# cape.net
KiCad netlist of a schematic drawn in EAGLE
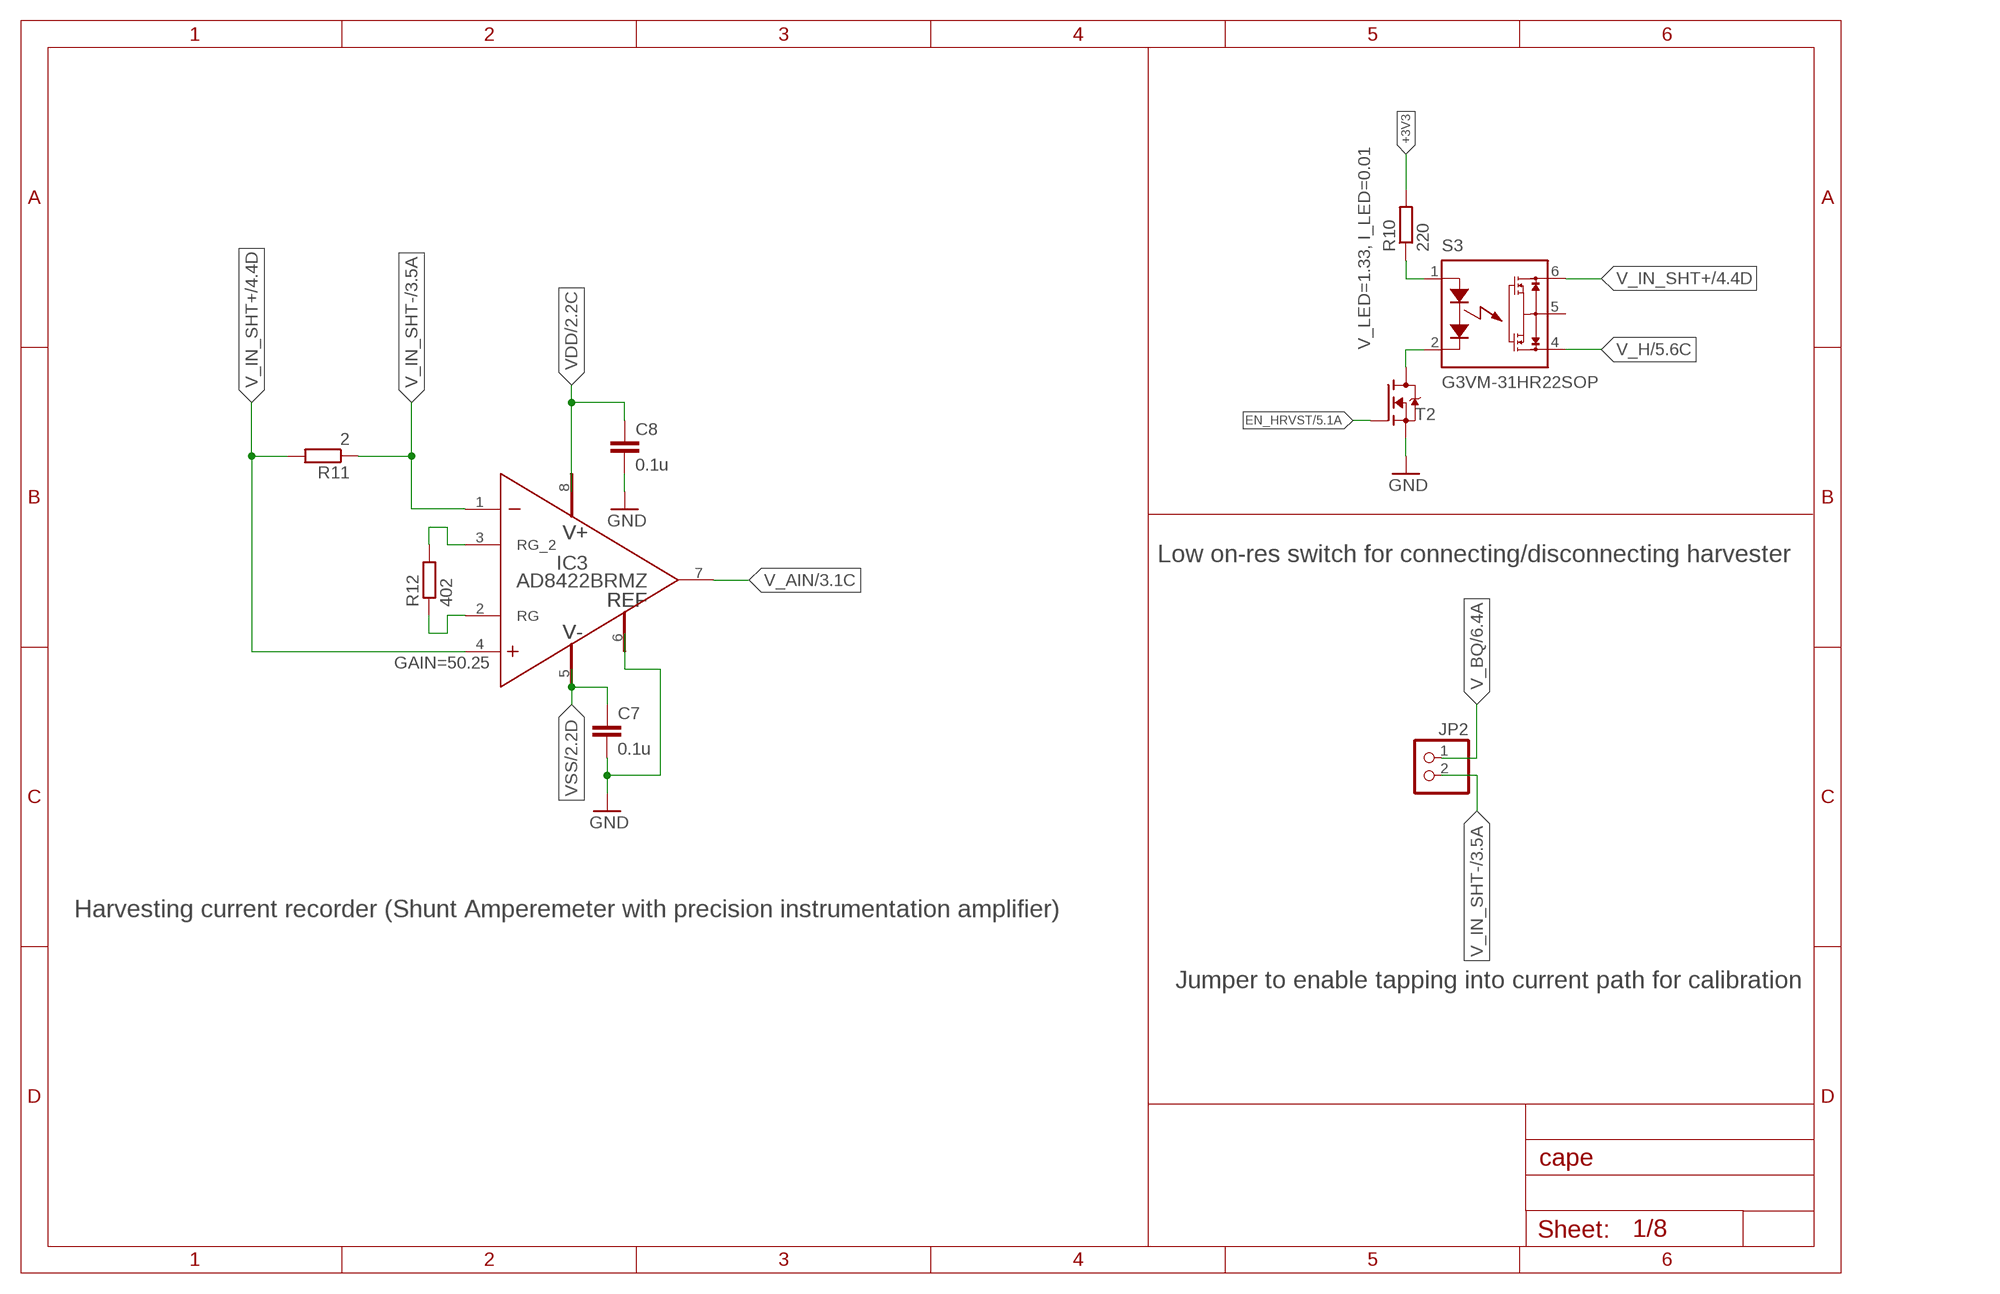
[diagram p0: schematic, sheet 1]
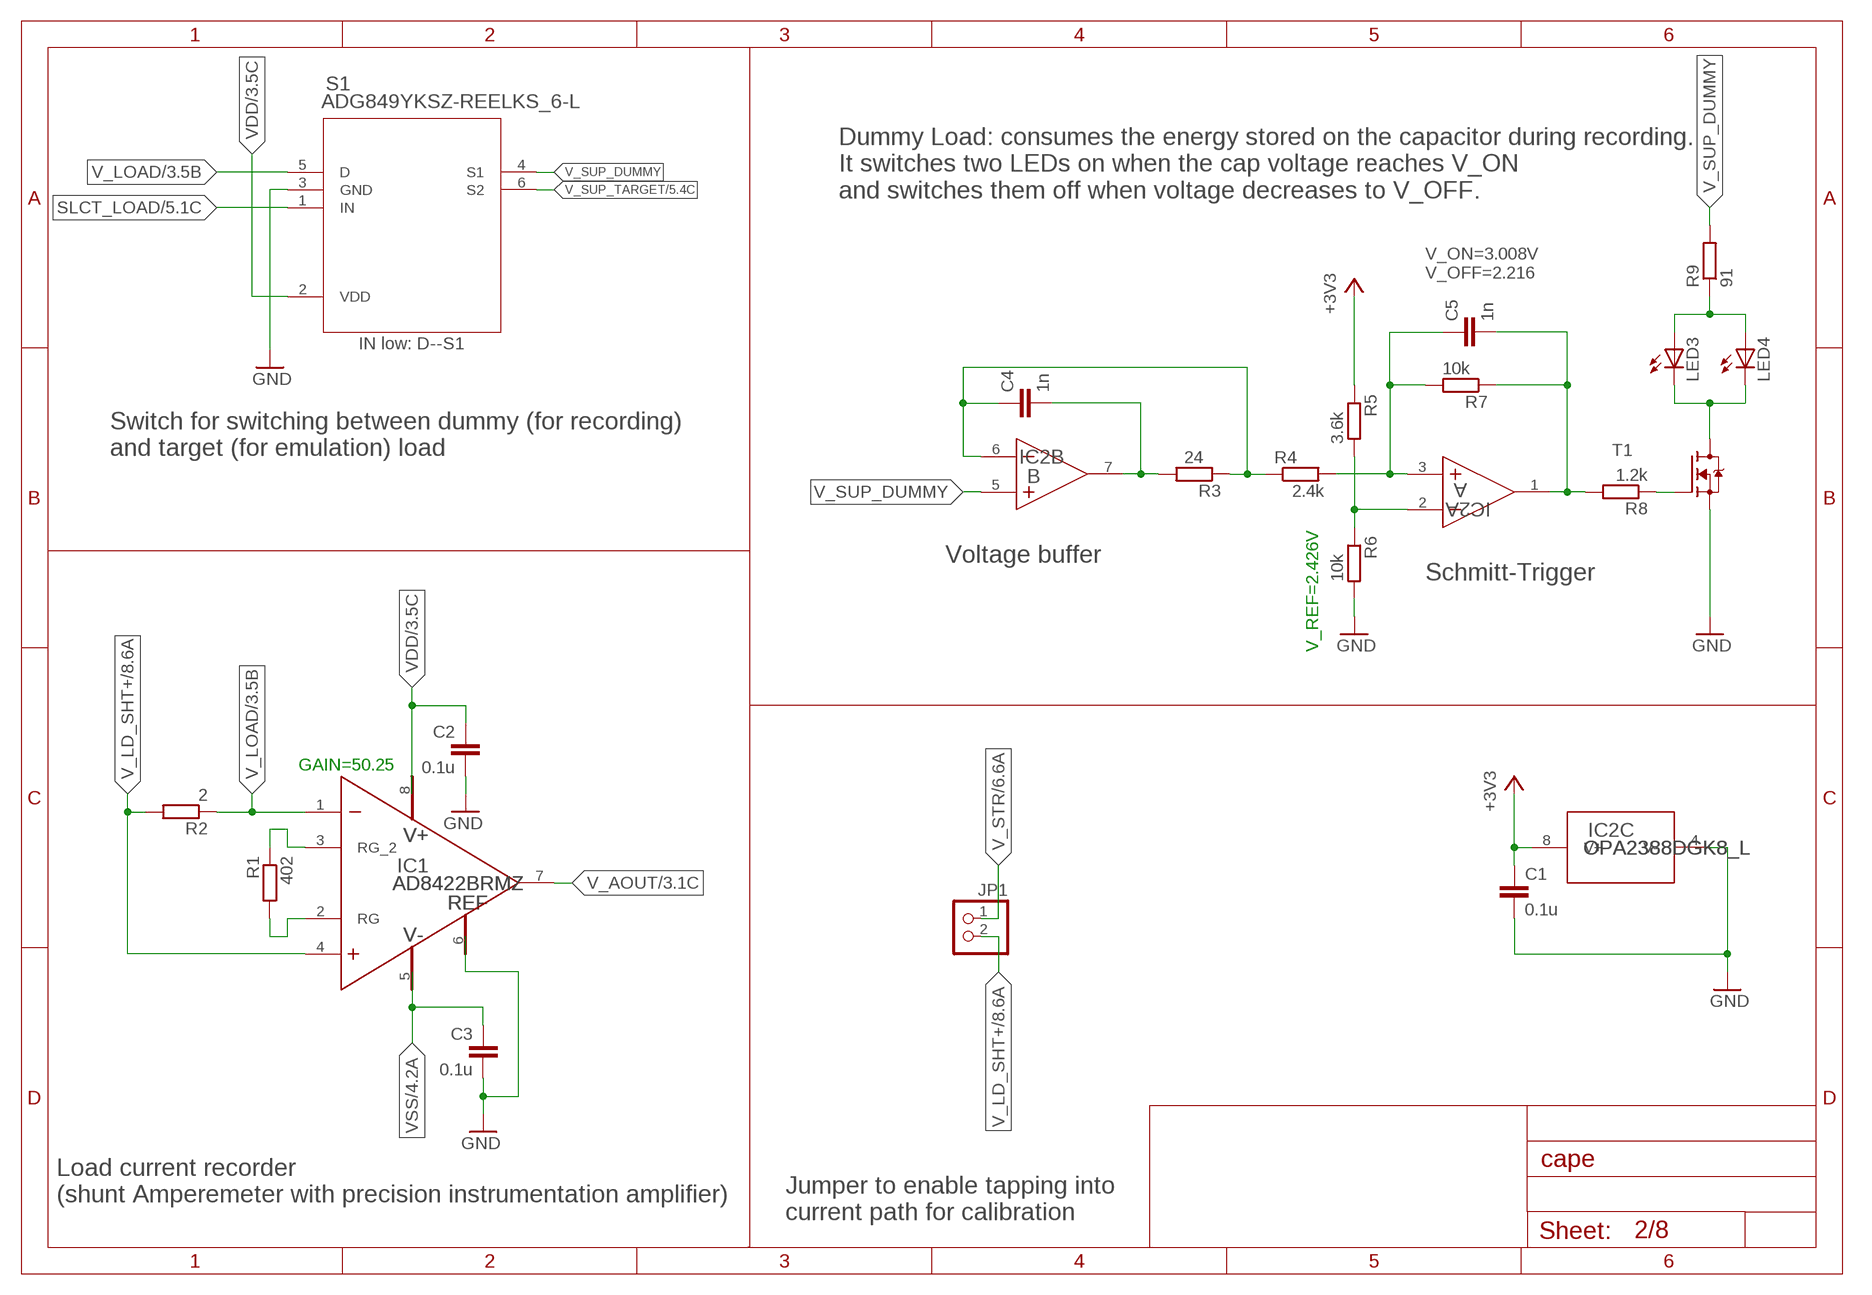
[diagram p1: schematic, sheet 2]
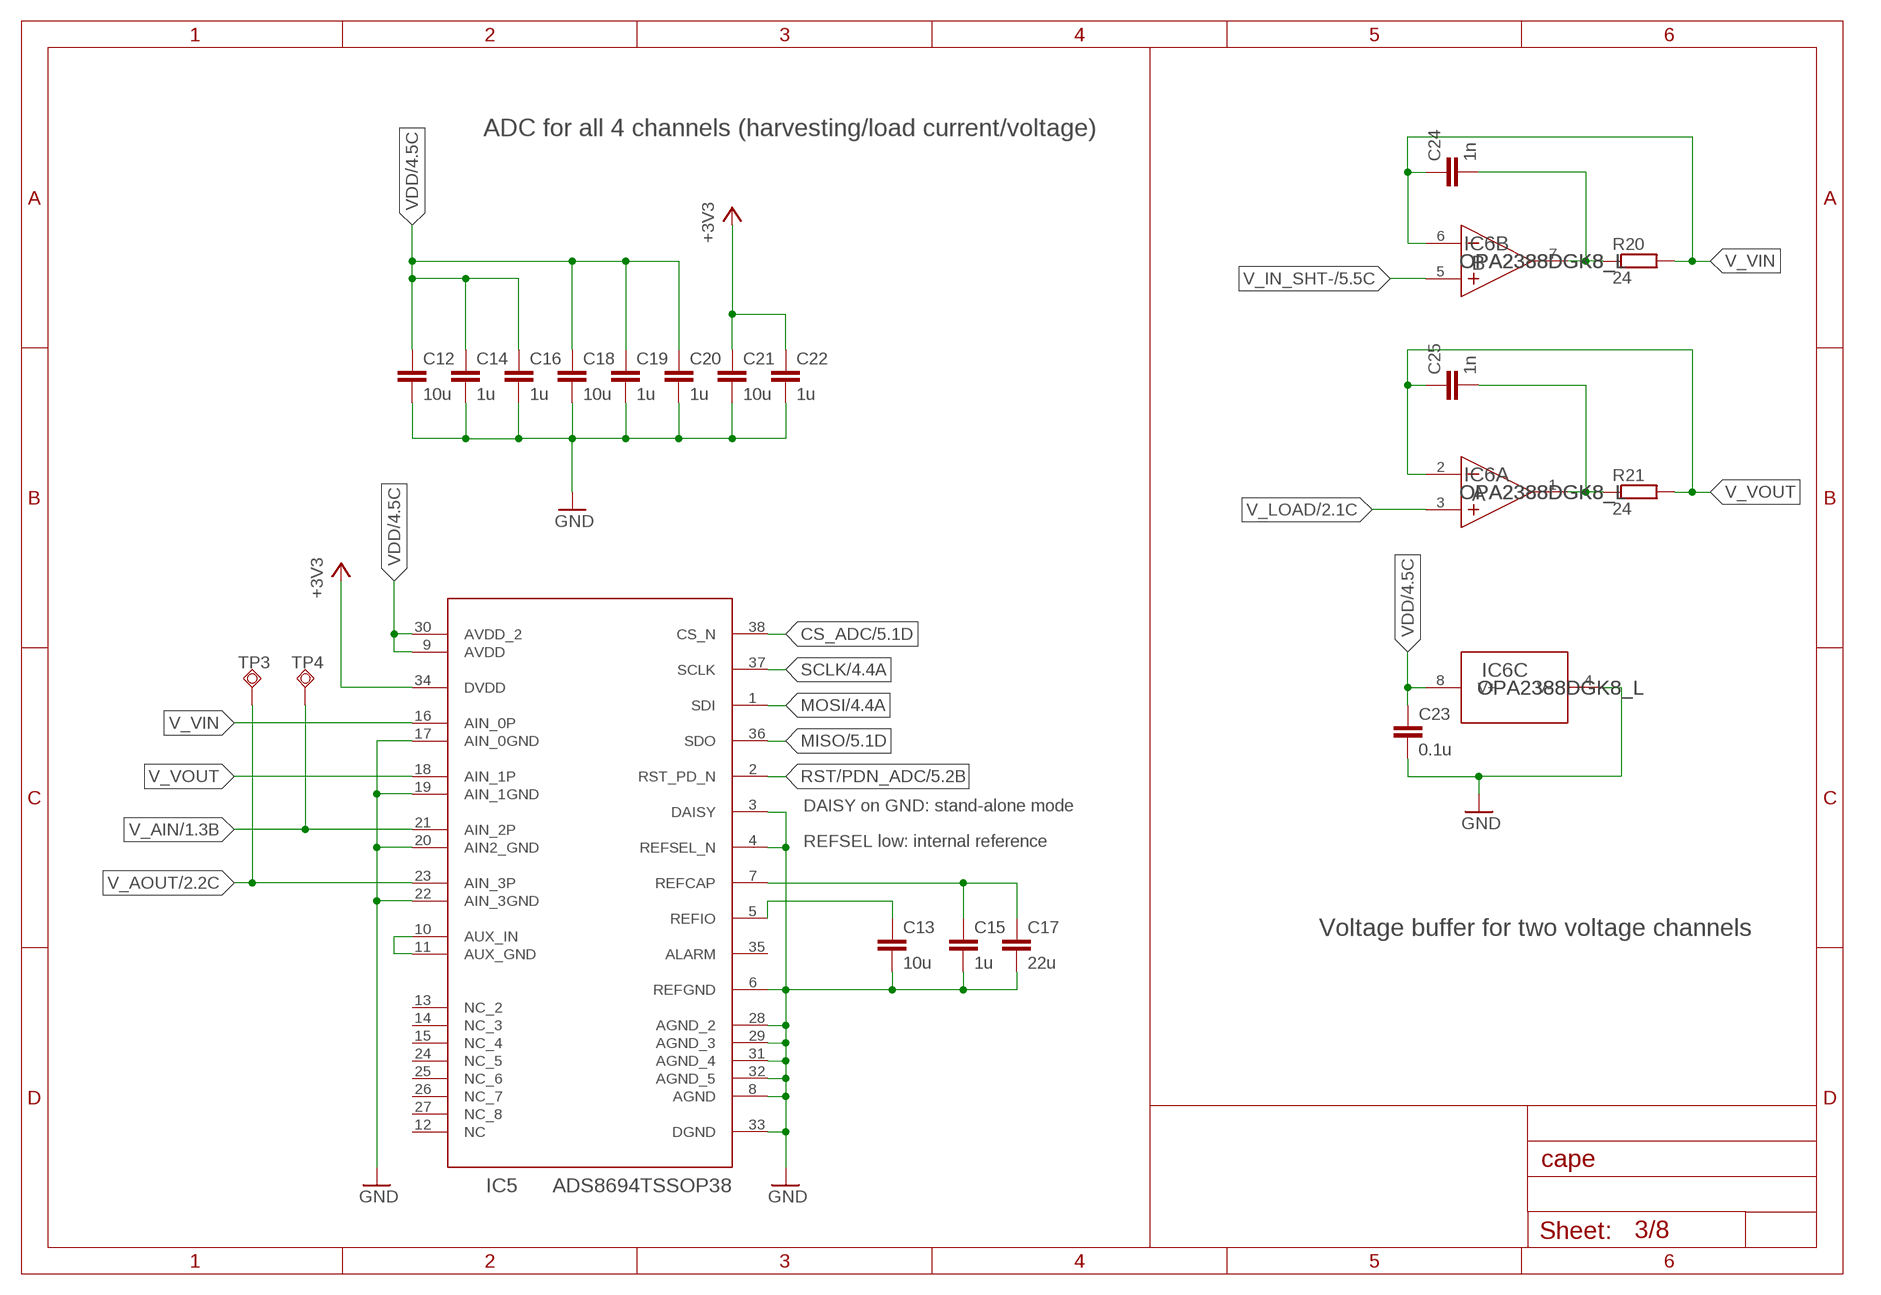
[diagram p2: schematic, sheet 3]
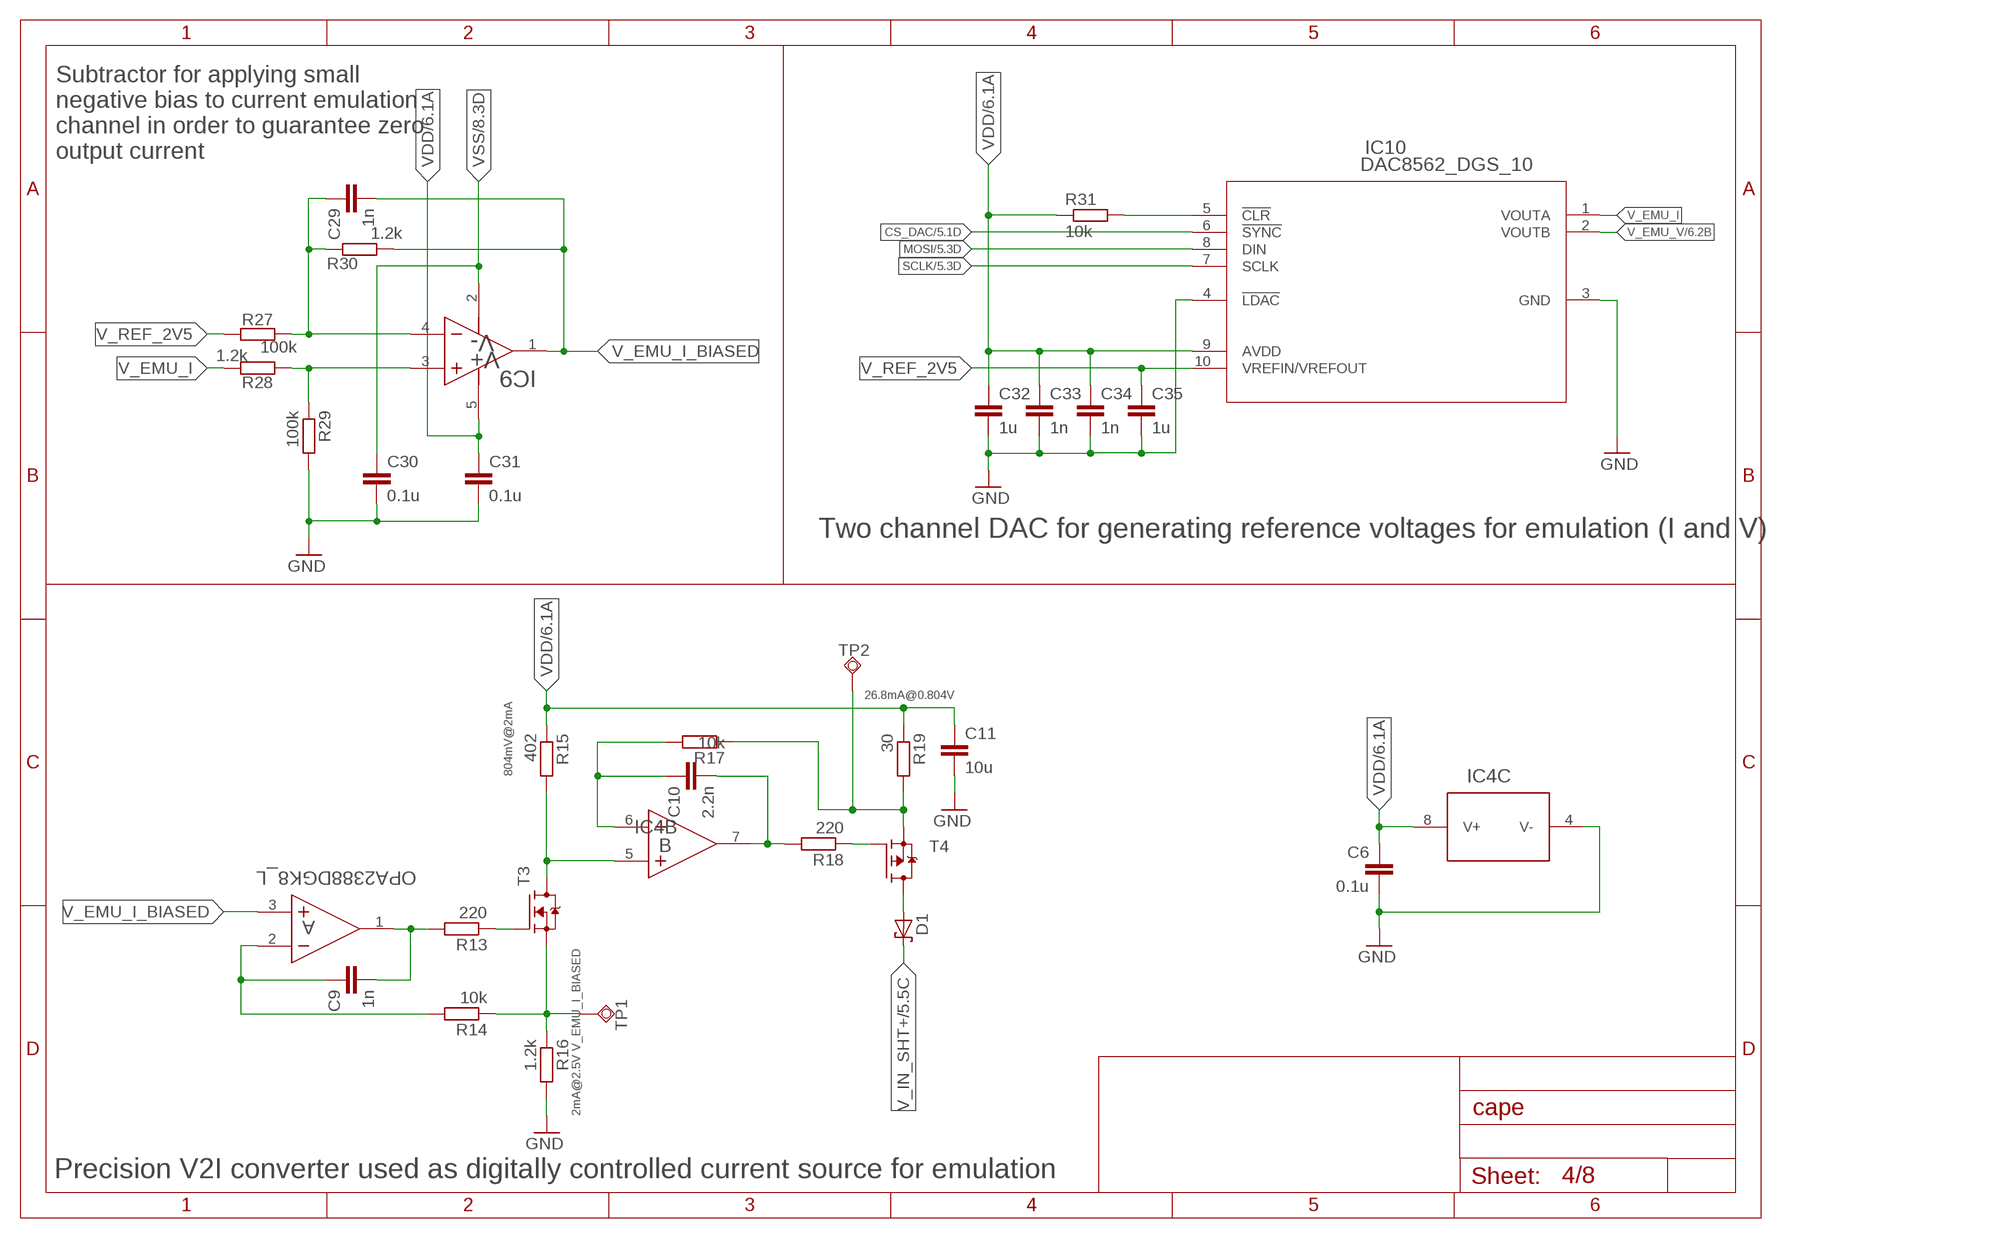
[diagram p3: schematic, sheet 4]
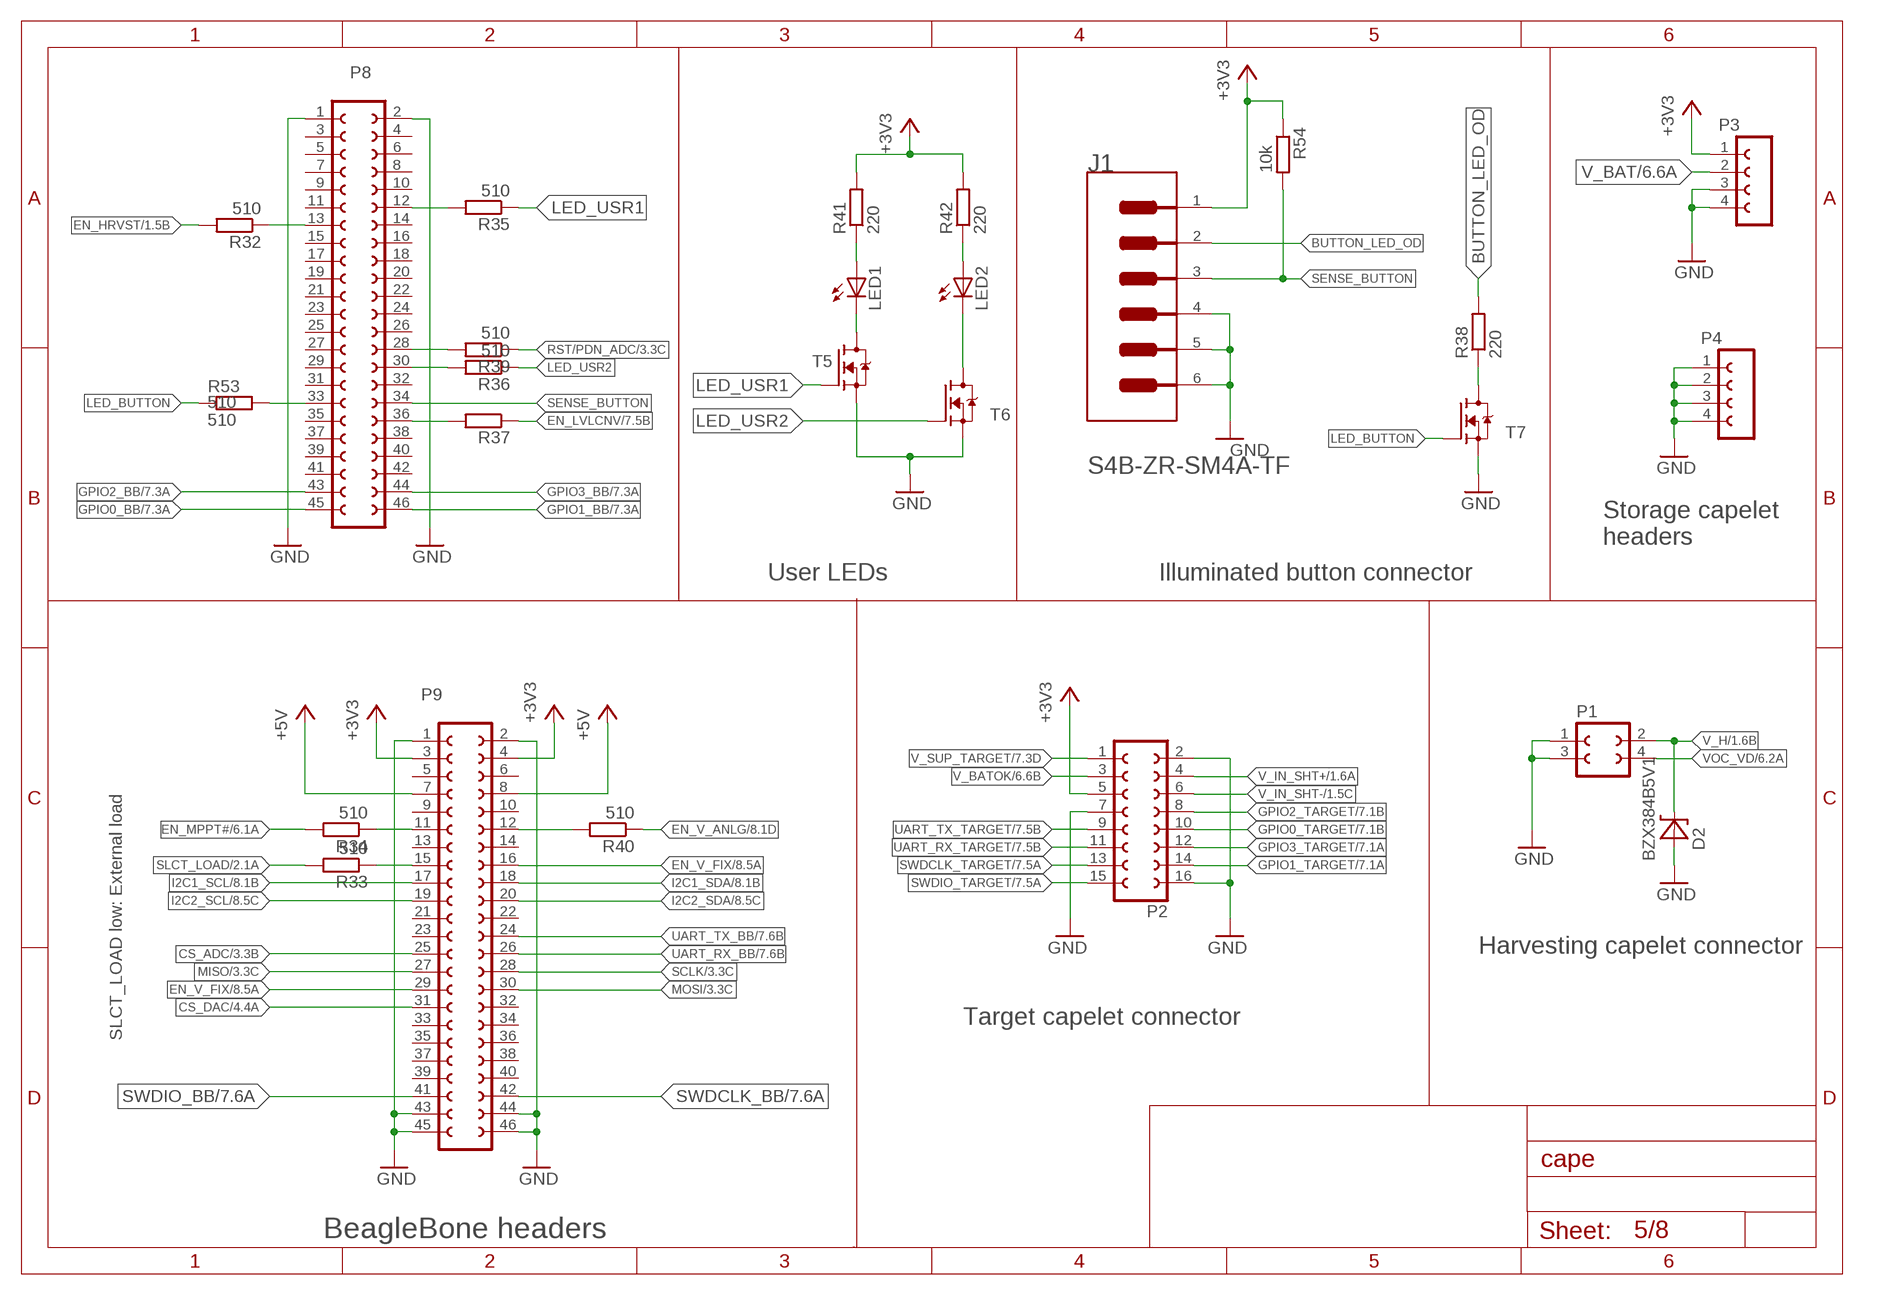
[diagram p4: schematic, sheet 5]
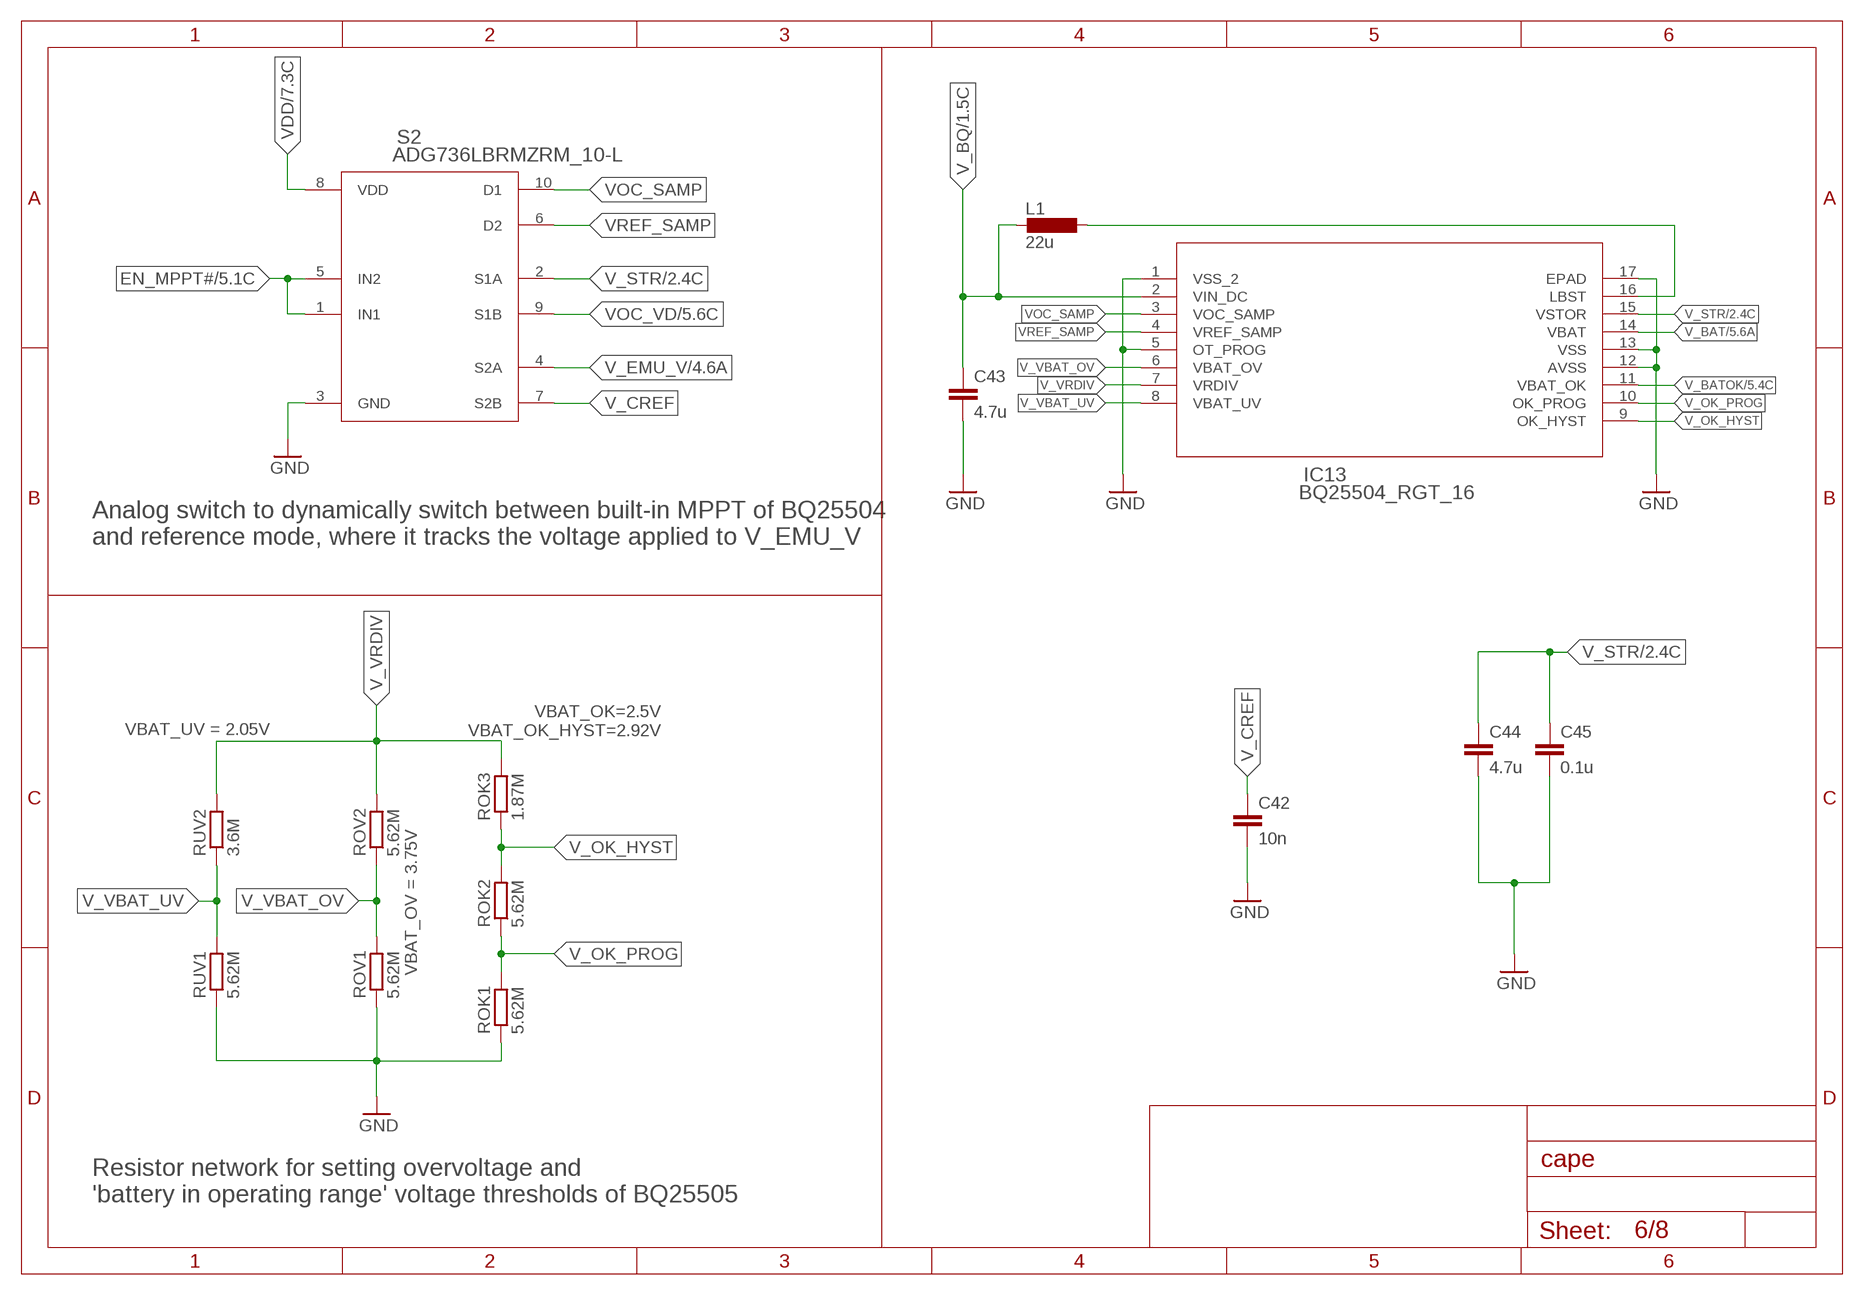
[diagram p5: schematic, sheet 6]
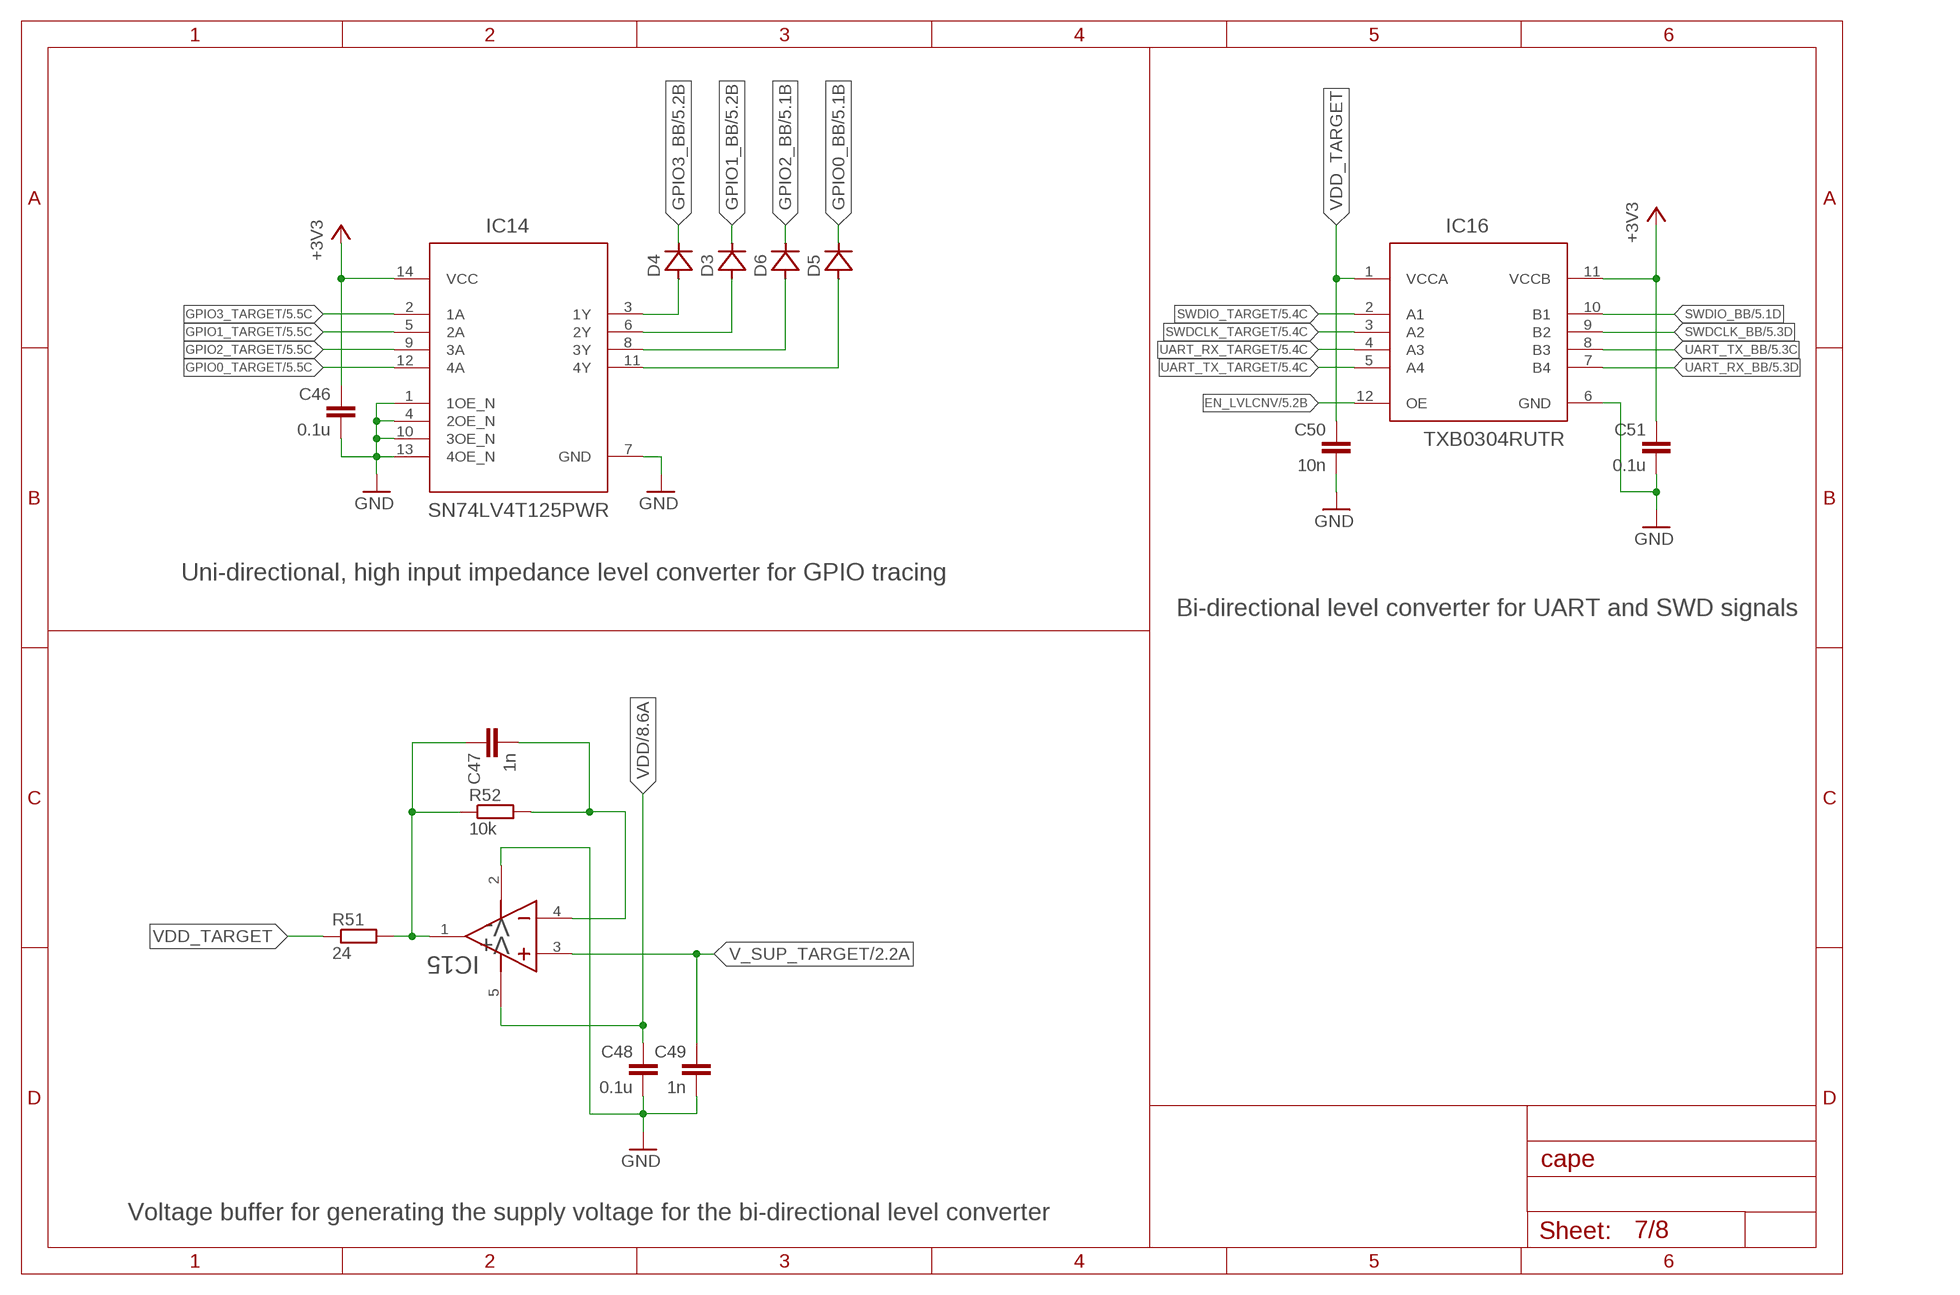
[diagram p6: schematic, sheet 7]
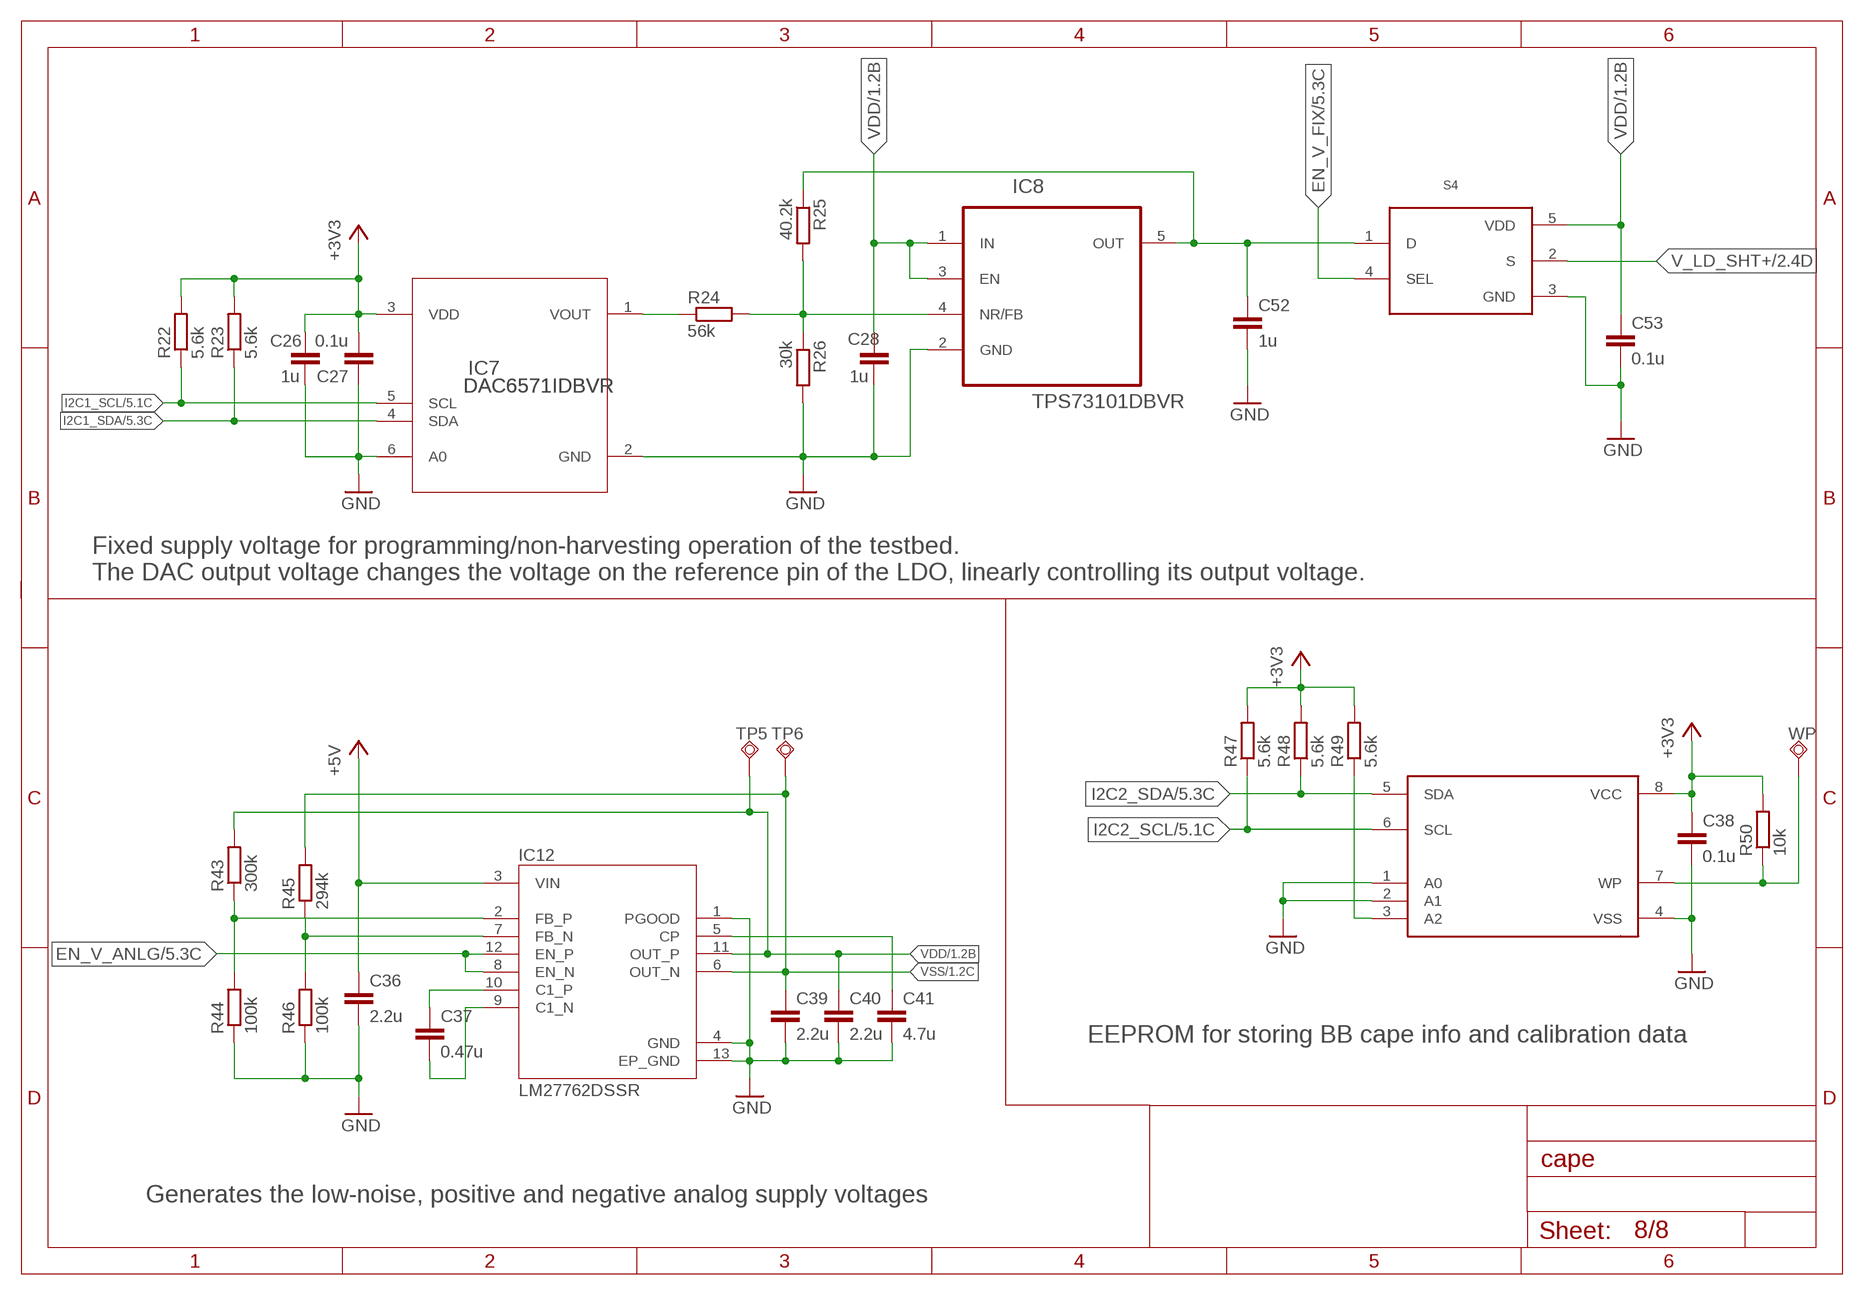
[diagram p7: schematic, sheet 8]

(export (version "E")
  (design (tool "Eeschema 10.0.6"))
  (components
    (comp (ref "C1")
      (value "0.1u")
      (footprint "eagle-import:CAPC1005X55")
      (libsource (lib "eagle-import") (part "C_SMD0402"))
    )
    (comp (ref "C2")
      (value "0.1u")
      (footprint "eagle-import:CAPC1005X55")
      (libsource (lib "eagle-import") (part "C_SMD0402"))
    )
    (comp (ref "C3")
      (value "0.1u")
      (footprint "eagle-import:CAPC1005X55")
      (libsource (lib "eagle-import") (part "C_SMD0402"))
    )
    (comp (ref "C4")
      (value "1n")
      (footprint "eagle-import:CAPC1005X55")
      (libsource (lib "eagle-import") (part "C_SMD0402"))
    )
    (comp (ref "C5")
      (value "1n")
      (footprint "eagle-import:CAPC1005X55")
      (libsource (lib "eagle-import") (part "C_SMD0402"))
    )
    (comp (ref "IC1")
      (value "AD8422BRMZ")
      (footprint "eagle-import:RM_8-L")
      (libsource (lib "eagle-import") (part "AD8422BRMZ"))
    )
    (comp (ref "IC2")
      (value "OPA2388DGK8_L")
      (footprint "eagle-import:DGK8-L")
      (libsource (lib "eagle-import") (part "OPA2388DGK8_L"))
    )
    (comp (ref "JP1")
      (value "PINHD-1X2")
      (footprint "eagle-import:1X02")
      (libsource (lib "eagle-import") (part "PINHD-1X2"))
    )
    (comp (ref "LED3")
      (value "598-8130-107FLED_0805")
      (footprint "eagle-import:LEDC2012X75")
      (libsource (lib "eagle-import") (part "598-8130-107FLED_0805"))
    )
    (comp (ref "LED4")
      (value "598-8130-107FLED_0805")
      (footprint "eagle-import:LEDC2012X75")
      (libsource (lib "eagle-import") (part "598-8130-107FLED_0805"))
    )
    (comp (ref "R1")
      (value "402")
      (footprint "eagle-import:RESC1608X55")
      (libsource (lib "eagle-import") (part "R_SMD0603"))
    )
    (comp (ref "R2")
      (value "2")
      (footprint "eagle-import:RESC1608X55")
      (libsource (lib "eagle-import") (part "R_SMD0603"))
    )
    (comp (ref "R3")
      (value "24")
      (footprint "eagle-import:RESC1005X40")
      (libsource (lib "eagle-import") (part "R_SMD0402"))
    )
    (comp (ref "R4")
      (value "2.4k")
      (footprint "eagle-import:RESC1005X40")
      (libsource (lib "eagle-import") (part "R_SMD0402"))
    )
    (comp (ref "R5")
      (value "3.6k")
      (footprint "eagle-import:RESC1005X40")
      (libsource (lib "eagle-import") (part "R_SMD0402"))
    )
    (comp (ref "R6")
      (value "10k")
      (footprint "eagle-import:RESC1005X40")
      (libsource (lib "eagle-import") (part "R_SMD0402"))
    )
    (comp (ref "R7")
      (value "10k")
      (footprint "eagle-import:RESC1005X40")
      (libsource (lib "eagle-import") (part "R_SMD0402"))
    )
    (comp (ref "R8")
      (value "1.2k")
      (footprint "eagle-import:RESC1005X40")
      (libsource (lib "eagle-import") (part "R_SMD0402"))
    )
    (comp (ref "R9")
      (value "91")
      (footprint "eagle-import:RESC1608X55")
      (libsource (lib "eagle-import") (part "R_SMD0603"))
    )
    (comp (ref "S1")
      (value "ADG849YKSZ-REELKS_6-L")
      (footprint "eagle-import:KS_6-L")
      (libsource (lib "eagle-import") (part "ADG849YKSZ-REELKS_6-L"))
    )
    (comp (ref "T1")
      (value "SI2374DSSOT23-VSHAY")
      (footprint "eagle-import:SOT95P237X112-3")
      (libsource (lib "eagle-import") (part "SI2374DSSOT23-VSHAY"))
    )
    (comp (ref "C26")
      (value "1u")
      (footprint "eagle-import:CAPC1608X95")
      (libsource (lib "eagle-import") (part "C_SMD0603"))
    )
    (comp (ref "C27")
      (value "0.1u")
      (footprint "eagle-import:CAPC1005X55")
      (libsource (lib "eagle-import") (part "C_SMD0402"))
    )
    (comp (ref "C28")
      (value "1u")
      (footprint "eagle-import:CAPC1608X95")
      (libsource (lib "eagle-import") (part "C_SMD0603"))
    )
    (comp (ref "C36")
      (value "2.2u")
      (footprint "eagle-import:CAPC2012X145")
      (libsource (lib "eagle-import") (part "C_SMD0805"))
    )
    (comp (ref "C37")
      (value "0.47u")
      (footprint "eagle-import:CAPC1608X95")
      (libsource (lib "eagle-import") (part "C_SMD0603"))
    )
    (comp (ref "C38")
      (value "0.1u")
      (footprint "eagle-import:CAPC1005X55")
      (libsource (lib "eagle-import") (part "C_SMD0402"))
    )
    (comp (ref "C39")
      (value "2.2u")
      (footprint "eagle-import:CAPC2012X145")
      (libsource (lib "eagle-import") (part "C_SMD0805"))
    )
    (comp (ref "C40")
      (value "2.2u")
      (footprint "eagle-import:CAPC2012X145")
      (libsource (lib "eagle-import") (part "C_SMD0805"))
    )
    (comp (ref "C41")
      (value "4.7u")
      (footprint "eagle-import:CAPC2012X145")
      (libsource (lib "eagle-import") (part "C_SMD0805"))
    )
    (comp (ref "C52")
      (value "1u")
      (footprint "eagle-import:CAPC1608X95")
      (libsource (lib "eagle-import") (part "shepherd_C_SMD0603"))
    )
    (comp (ref "C53")
      (value "0.1u")
      (footprint "eagle-import:CAPC1005X55")
      (libsource (lib "eagle-import") (part "C_SMD0402"))
    )
    (comp (ref "IC7")
      (value "DAC6571IDBVR")
      (footprint "eagle-import:DAC6571IDBVR")
      (libsource (lib "eagle-import") (part "DAC6571IDBVR"))
    )
    (comp (ref "IC8")
      (value "TPS73101DBVR")
      (footprint "eagle-import:SOT95P280X145-5N")
      (fields (field (name "MF") "Texas Instruments"))
      (libsource (lib "eagle-import") (part "TPS73101DBVR"))
    )
    (comp (ref "IC11")
      (value "CAT24C256WI-GT3")
      (footprint "eagle-import:SO08")
      (libsource (lib "eagle-import") (part "CAT24C256WI-GT3"))
    )
    (comp (ref "IC12")
      (value "LM27762DSSR")
      (footprint "eagle-import:VREG_LM27762DSSR")
      (fields (field (name "MF") "Texas Instruments"))
      (libsource (lib "eagle-import") (part "LM27762DSSR"))
    )
    (comp (ref "R22")
      (value "5.6k")
      (footprint "eagle-import:RESC1005X40")
      (libsource (lib "eagle-import") (part "R_SMD0402"))
    )
    (comp (ref "R23")
      (value "5.6k")
      (footprint "eagle-import:RESC1005X40")
      (libsource (lib "eagle-import") (part "R_SMD0402"))
    )
    (comp (ref "R24")
      (value "56k")
      (footprint "eagle-import:RESC1005X40")
      (libsource (lib "eagle-import") (part "R_SMD0402"))
    )
    (comp (ref "R25")
      (value "40.2k")
      (footprint "eagle-import:RESC1005X40")
      (libsource (lib "eagle-import") (part "R_SMD0402"))
    )
    (comp (ref "R26")
      (value "30k")
      (footprint "eagle-import:RESC1005X40")
      (libsource (lib "eagle-import") (part "R_SMD0402"))
    )
    (comp (ref "R43")
      (value "300k")
      (footprint "eagle-import:RESC1005X40")
      (libsource (lib "eagle-import") (part "R_SMD0402"))
    )
    (comp (ref "R44")
      (value "100k")
      (footprint "eagle-import:RESC1005X40")
      (libsource (lib "eagle-import") (part "R_SMD0402"))
    )
    (comp (ref "R45")
      (value "294k")
      (footprint "eagle-import:RESC1005X40")
      (libsource (lib "eagle-import") (part "R_SMD0402"))
    )
    (comp (ref "R46")
      (value "100k")
      (footprint "eagle-import:RESC1005X40")
      (libsource (lib "eagle-import") (part "R_SMD0402"))
    )
    (comp (ref "R47")
      (value "5.6k")
      (footprint "eagle-import:RESC1005X40")
      (libsource (lib "eagle-import") (part "R_SMD0402"))
    )
    (comp (ref "R48")
      (value "5.6k")
      (footprint "eagle-import:RESC1005X40")
      (libsource (lib "eagle-import") (part "R_SMD0402"))
    )
    (comp (ref "R49")
      (value "5.6k")
      (footprint "eagle-import:RESC1005X40")
      (libsource (lib "eagle-import") (part "R_SMD0402"))
    )
    (comp (ref "R50")
      (value "10k")
      (footprint "eagle-import:RESC1005X40")
      (libsource (lib "eagle-import") (part "R_SMD0402"))
    )
    (comp (ref "S4")
      (value "TMUX1101DCK")
      (footprint "eagle-import:DCK5")
      (libsource (lib "eagle-import") (part "TMUX1101DCK"))
    )
    (comp (ref "TP5")
      (value "TPSQTP06R")
      (footprint "eagle-import:TP06R")
      (libsource (lib "eagle-import") (part "TPSQTP06R"))
    )
    (comp (ref "TP6")
      (value "TPSQTP06R")
      (footprint "eagle-import:TP06R")
      (libsource (lib "eagle-import") (part "TPSQTP06R"))
    )
    (comp (ref "WP")
      (value "TPSQTP06R")
      (footprint "eagle-import:TP06R")
      (libsource (lib "eagle-import") (part "TPSQTP06R"))
    )
    (comp (ref "C6")
      (value "0.1u")
      (footprint "eagle-import:CAPC1005X55")
      (libsource (lib "eagle-import") (part "C_SMD0402"))
    )
    (comp (ref "C9")
      (value "1n")
      (footprint "eagle-import:CAPC1005X55")
      (libsource (lib "eagle-import") (part "C_SMD0402"))
    )
    (comp (ref "C10")
      (value "2.2n")
      (footprint "eagle-import:CAPC1005X55")
      (libsource (lib "eagle-import") (part "C_SMD0402"))
    )
    (comp (ref "C11")
      (value "10u")
      (footprint "eagle-import:CAPC2012X145")
      (libsource (lib "eagle-import") (part "C_SMD0805"))
    )
    (comp (ref "C29")
      (value "1n")
      (footprint "eagle-import:CAPC1005X55")
      (libsource (lib "eagle-import") (part "C_SMD0402"))
    )
    (comp (ref "C30")
      (value "0.1u")
      (footprint "eagle-import:CAPC1005X55")
      (libsource (lib "eagle-import") (part "C_SMD0402"))
    )
    (comp (ref "C31")
      (value "0.1u")
      (footprint "eagle-import:CAPC1005X55")
      (libsource (lib "eagle-import") (part "C_SMD0402"))
    )
    (comp (ref "C32")
      (value "1u")
      (footprint "eagle-import:CAPC1608X95")
      (libsource (lib "eagle-import") (part "C_SMD0603"))
    )
    (comp (ref "C33")
      (value "1n")
      (footprint "eagle-import:CAPC1005X55")
      (libsource (lib "eagle-import") (part "C_SMD0402"))
    )
    (comp (ref "C34")
      (value "1n")
      (footprint "eagle-import:CAPC1005X55")
      (libsource (lib "eagle-import") (part "C_SMD0402"))
    )
    (comp (ref "C35")
      (value "1u")
      (footprint "eagle-import:CAPC1608X95")
      (libsource (lib "eagle-import") (part "C_SMD0603"))
    )
    (comp (ref "D1")
      (value "BAT43WS-HE3SOD-323")
      (footprint "eagle-import:SOD2513X110")
      (libsource (lib "eagle-import") (part "BAT43WS-HE3SOD-323"))
    )
    (comp (ref "IC4")
      (value "OPA2388DGK8_L")
      (footprint "eagle-import:DGK8-L")
      (libsource (lib "eagle-import") (part "OPA2388DGK8_L"))
    )
    (comp (ref "IC9")
      (value "LMP7701MF")
      (footprint "eagle-import:DBV5-L")
      (libsource (lib "eagle-import") (part "LMP7701MF"))
    )
    (comp (ref "IC10")
      (value "DAC8562_DGS_10")
      (footprint "eagle-import:DGS10")
      (libsource (lib "eagle-import") (part "DAC8562_DGS_10"))
    )
    (comp (ref "R13")
      (value "220")
      (footprint "eagle-import:RESC1608X55")
      (libsource (lib "eagle-import") (part "R_SMD0603"))
    )
    (comp (ref "R14")
      (value "10k")
      (footprint "eagle-import:RESC1005X40")
      (libsource (lib "eagle-import") (part "R_SMD0402"))
    )
    (comp (ref "R15")
      (value "402")
      (footprint "eagle-import:RESC1608X55")
      (libsource (lib "eagle-import") (part "R_SMD0603"))
    )
    (comp (ref "R16")
      (value "1.2k")
      (footprint "eagle-import:RESC1005X40")
      (libsource (lib "eagle-import") (part "R_SMD0402"))
    )
    (comp (ref "R17")
      (value "10k")
      (footprint "eagle-import:RESC1005X40")
      (libsource (lib "eagle-import") (part "R_SMD0402"))
    )
    (comp (ref "R18")
      (value "220")
      (footprint "eagle-import:RESC1608X55")
      (libsource (lib "eagle-import") (part "R_SMD0603"))
    )
    (comp (ref "R19")
      (value "30")
      (footprint "eagle-import:RESC1005X40")
      (libsource (lib "eagle-import") (part "R_SMD0402"))
    )
    (comp (ref "R27")
      (value "100k")
      (footprint "eagle-import:RESC1005X40")
      (libsource (lib "eagle-import") (part "R_SMD0402"))
    )
    (comp (ref "R28")
      (value "1.2k")
      (footprint "eagle-import:RESC1005X40")
      (libsource (lib "eagle-import") (part "R_SMD0402"))
    )
    (comp (ref "R29")
      (value "100k")
      (footprint "eagle-import:RESC1005X40")
      (libsource (lib "eagle-import") (part "R_SMD0402"))
    )
    (comp (ref "R30")
      (value "1.2k")
      (footprint "eagle-import:RESC1005X40")
      (libsource (lib "eagle-import") (part "R_SMD0402"))
    )
    (comp (ref "R31")
      (value "10k")
      (footprint "eagle-import:RESC1005X40")
      (libsource (lib "eagle-import") (part "R_SMD0402"))
    )
    (comp (ref "T3")
      (value "SI2374DSSOT23-VSHAY")
      (footprint "eagle-import:SOT95P237X112-3")
      (libsource (lib "eagle-import") (part "SI2374DSSOT23-VSHAY"))
    )
    (comp (ref "T4")
      (value "SI2307SOT23-VSHAY")
      (footprint "eagle-import:SOT95P237X112-3")
      (libsource (lib "eagle-import") (part "SI2307SOT23-VSHAY"))
    )
    (comp (ref "TP1")
      (value "TPSQTP06R")
      (footprint "eagle-import:TP06R")
      (libsource (lib "eagle-import") (part "TPSQTP06R"))
    )
    (comp (ref "TP2")
      (value "TPSQTP06R")
      (footprint "eagle-import:TP06R")
      (libsource (lib "eagle-import") (part "TPSQTP06R"))
    )
    (comp (ref "C42")
      (value "10n")
      (footprint "eagle-import:CAPC1005X55")
      (libsource (lib "eagle-import") (part "C_SMD0402"))
    )
    (comp (ref "C43")
      (value "4.7u")
      (footprint "eagle-import:CAPC2012X145")
      (libsource (lib "eagle-import") (part "C_SMD0805"))
    )
    (comp (ref "C44")
      (value "4.7u")
      (footprint "eagle-import:CAPC2012X145")
      (libsource (lib "eagle-import") (part "C_SMD0805"))
    )
    (comp (ref "C45")
      (value "0.1u")
      (footprint "eagle-import:CAPC1005X55")
      (libsource (lib "eagle-import") (part "C_SMD0402"))
    )
    (comp (ref "IC13")
      (value "BQ25504_RGT_16")
      (footprint "eagle-import:RGT16_1P7X1P7")
      (libsource (lib "eagle-import") (part "BQ25504_RGT_16"))
    )
    (comp (ref "L1")
      (value "22u")
      (footprint "eagle-import:L3225P")
      (libsource (lib "eagle-import") (part "L-EUL3225P"))
    )
    (comp (ref "ROK1")
      (value "5.62M")
      (footprint "eagle-import:RESC1608X55")
      (libsource (lib "eagle-import") (part "R_SMD0603"))
    )
    (comp (ref "ROK2")
      (value "5.62M")
      (footprint "eagle-import:RESC1608X55")
      (libsource (lib "eagle-import") (part "R_SMD0603"))
    )
    (comp (ref "ROK3")
      (value "1.87M")
      (footprint "eagle-import:RESC1608X55")
      (libsource (lib "eagle-import") (part "R_SMD0603"))
    )
    (comp (ref "ROV1")
      (value "5.62M")
      (footprint "eagle-import:RESC1608X55")
      (libsource (lib "eagle-import") (part "R_SMD0603"))
    )
    (comp (ref "ROV2")
      (value "5.62M")
      (footprint "eagle-import:RESC1608X55")
      (libsource (lib "eagle-import") (part "R_SMD0603"))
    )
    (comp (ref "RUV1")
      (value "5.62M")
      (footprint "eagle-import:RESC1608X55")
      (libsource (lib "eagle-import") (part "R_SMD0603"))
    )
    (comp (ref "RUV2")
      (value "3.6M")
      (footprint "eagle-import:RESC1608X55")
      (libsource (lib "eagle-import") (part "R_SMD0603"))
    )
    (comp (ref "S2")
      (value "ADG736LBRMZRM_10-L")
      (footprint "eagle-import:RM_10-L")
      (libsource (lib "eagle-import") (part "ADG736LBRMZRM_10-L"))
    )
    (comp (ref "D2")
      (value "BZX384B5V1")
      (footprint "eagle-import:SOD2513X110")
      (libsource (lib "eagle-import") (part "BZX384B5V1"))
    )
    (comp (ref "J1")
      (value "JST_S4B-ZR-SM4A-TFJST_S4B-ZR-SM4A-TF_0_0")
      (footprint "eagle-import:JST_S4B-ZR-SM4A-TF_0")
      (fields
        (field (name "DIGIKEY_PART_NUMBER") "455-1695-1-ND")
        (field (name "MF") "JST")
        (field (name "MOUSER_PART_NUMBER") "538-502585-0470")
      )
      (libsource (lib "eagle-import") (part "JST_S4B-ZR-SM4A-TFJST_S4B-ZR-SM4A-TF_0_0"))
    )
    (comp (ref "LED1")
      (value "598-8130-107FLED_0805")
      (footprint "eagle-import:LEDC2012X75")
      (libsource (lib "eagle-import") (part "598-8130-107FLED_0805"))
    )
    (comp (ref "LED2")
      (value "598-8130-107FLED_0805")
      (footprint "eagle-import:LEDC2012X75")
      (libsource (lib "eagle-import") (part "598-8130-107FLED_0805"))
    )
    (comp (ref "P1")
      (value "FE02-2")
      (footprint "eagle-import:FE02-2")
      (libsource (lib "eagle-import") (part "FE02-2"))
    )
    (comp (ref "P2")
      (value "FE08-2")
      (footprint "eagle-import:FE08-2")
      (libsource (lib "eagle-import") (part "FE08-2"))
    )
    (comp (ref "P3")
      (value "FE04-1")
      (footprint "eagle-import:FE04-1")
      (libsource (lib "eagle-import") (part "FE04-1"))
    )
    (comp (ref "P4")
      (value "FE04-1")
      (footprint "eagle-import:FE04-1")
      (libsource (lib "eagle-import") (part "FE04-1"))
    )
    (comp (ref "P8")
      (value "FE23-2")
      (footprint "eagle-import:FE23-2")
      (libsource (lib "eagle-import") (part "FE23-2"))
    )
    (comp (ref "P9")
      (value "FE23-2")
      (footprint "eagle-import:FE23-2")
      (libsource (lib "eagle-import") (part "FE23-2"))
    )
    (comp (ref "R32")
      (value "510")
      (footprint "eagle-import:RESC1005X40")
      (libsource (lib "eagle-import") (part "R_SMD0402"))
    )
    (comp (ref "R33")
      (value "510")
      (footprint "eagle-import:RESC1005X40")
      (libsource (lib "eagle-import") (part "R_SMD0402"))
    )
    (comp (ref "R34")
      (value "510")
      (footprint "eagle-import:RESC1005X40")
      (libsource (lib "eagle-import") (part "R_SMD0402"))
    )
    (comp (ref "R35")
      (value "510")
      (footprint "eagle-import:RESC1005X40")
      (libsource (lib "eagle-import") (part "R_SMD0402"))
    )
    (comp (ref "R36")
      (value "510")
      (footprint "eagle-import:RESC1005X40")
      (libsource (lib "eagle-import") (part "R_SMD0402"))
    )
    (comp (ref "R37")
      (value "510")
      (footprint "eagle-import:RESC1005X40")
      (libsource (lib "eagle-import") (part "R_SMD0402"))
    )
    (comp (ref "R38")
      (value "220")
      (footprint "eagle-import:RESC1608X55")
      (libsource (lib "eagle-import") (part "R_SMD0603"))
    )
    (comp (ref "R39")
      (value "510")
      (footprint "eagle-import:RESC1005X40")
      (libsource (lib "eagle-import") (part "R_SMD0402"))
    )
    (comp (ref "R40")
      (value "510")
      (footprint "eagle-import:RESC1005X40")
      (libsource (lib "eagle-import") (part "R_SMD0402"))
    )
    (comp (ref "R41")
      (value "220")
      (footprint "eagle-import:RESC1608X55")
      (libsource (lib "eagle-import") (part "R_SMD0603"))
    )
    (comp (ref "R42")
      (value "220")
      (footprint "eagle-import:RESC1608X55")
      (libsource (lib "eagle-import") (part "R_SMD0603"))
    )
    (comp (ref "R53")
      (value "510")
      (footprint "eagle-import:RESC1005X40")
      (libsource (lib "eagle-import") (part "R_SMD0402"))
    )
    (comp (ref "R54")
      (value "10k")
      (footprint "eagle-import:RESC1005X40")
      (libsource (lib "eagle-import") (part "R_SMD0402"))
    )
    (comp (ref "T5")
      (value "SI2374DSSOT23-VSHAY")
      (footprint "eagle-import:SOT95P237X112-3")
      (libsource (lib "eagle-import") (part "SI2374DSSOT23-VSHAY"))
    )
    (comp (ref "T6")
      (value "SI2374DSSOT23-VSHAY")
      (footprint "eagle-import:SOT95P237X112-3")
      (libsource (lib "eagle-import") (part "SI2374DSSOT23-VSHAY"))
    )
    (comp (ref "T7")
      (value "SI2374DSSOT23-VSHAY")
      (footprint "eagle-import:SOT95P237X112-3")
      (libsource (lib "eagle-import") (part "SI2374DSSOT23-VSHAY"))
    )
    (comp (ref "C7")
      (value "0.1u")
      (footprint "eagle-import:CAPC1005X55")
      (libsource (lib "eagle-import") (part "C_SMD0402"))
    )
    (comp (ref "C8")
      (value "0.1u")
      (footprint "eagle-import:CAPC1005X55")
      (libsource (lib "eagle-import") (part "C_SMD0402"))
    )
    (comp (ref "IC3")
      (value "AD8422BRMZ")
      (footprint "eagle-import:RM_8-L")
      (libsource (lib "eagle-import") (part "AD8422BRMZ"))
    )
    (comp (ref "JP2")
      (value "PINHD-1X2")
      (footprint "eagle-import:1X02")
      (libsource (lib "eagle-import") (part "PINHD-1X2"))
    )
    (comp (ref "R10")
      (value "220")
      (footprint "eagle-import:RESC1608X55")
      (libsource (lib "eagle-import") (part "R_SMD0603"))
    )
    (comp (ref "R11")
      (value "2")
      (footprint "eagle-import:RESC1608X55")
      (libsource (lib "eagle-import") (part "R_SMD0603"))
    )
    (comp (ref "R12")
      (value "402")
      (footprint "eagle-import:RESC1608X55")
      (libsource (lib "eagle-import") (part "R_SMD0603"))
    )
    (comp (ref "S3")
      (value "G3VM-31HR22SOP")
      (footprint "eagle-import:SOP06")
      (libsource (lib "eagle-import") (part "G3VM-31HRSOP22"))
    )
    (comp (ref "T2")
      (value "SI2374DSSOT23-VSHAY")
      (footprint "eagle-import:SOT95P237X112-3")
      (libsource (lib "eagle-import") (part "SI2374DSSOT23-VSHAY"))
    )
    (comp (ref "C46")
      (value "0.1u")
      (footprint "eagle-import:CAPC1005X55")
      (libsource (lib "eagle-import") (part "C_SMD0402"))
    )
    (comp (ref "C47")
      (value "1n")
      (footprint "eagle-import:CAPC1005X55")
      (libsource (lib "eagle-import") (part "C_SMD0402"))
    )
    (comp (ref "C48")
      (value "0.1u")
      (footprint "eagle-import:CAPC1005X55")
      (libsource (lib "eagle-import") (part "C_SMD0402"))
    )
    (comp (ref "C49")
      (value "1n")
      (footprint "eagle-import:CAPC1005X55")
      (libsource (lib "eagle-import") (part "C_SMD0402"))
    )
    (comp (ref "C50")
      (value "10n")
      (footprint "eagle-import:CAPC1005X55")
      (libsource (lib "eagle-import") (part "C_SMD0402"))
    )
    (comp (ref "C51")
      (value "0.1u")
      (footprint "eagle-import:CAPC1005X55")
      (libsource (lib "eagle-import") (part "C_SMD0402"))
    )
    (comp (ref "D3")
      (value "ACDBQC0130L-HF0402")
      (footprint "eagle-import:DIOC1005X55N")
      (libsource (lib "eagle-import") (part "ACDBQC0130L-HF0402"))
    )
    (comp (ref "D4")
      (value "ACDBQC0130L-HF0402")
      (footprint "eagle-import:DIOC1005X55N")
      (libsource (lib "eagle-import") (part "ACDBQC0130L-HF0402"))
    )
    (comp (ref "D5")
      (value "ACDBQC0130L-HF0402")
      (footprint "eagle-import:DIOC1005X55N")
      (libsource (lib "eagle-import") (part "ACDBQC0130L-HF0402"))
    )
    (comp (ref "D6")
      (value "ACDBQC0130L-HF0402")
      (footprint "eagle-import:DIOC1005X55N")
      (libsource (lib "eagle-import") (part "ACDBQC0130L-HF0402"))
    )
    (comp (ref "IC14")
      (value "SN74LV4T125PWR")
      (footprint "eagle-import:PW0014A_N")
      (libsource (lib "eagle-import") (part "SN74LV4T125PWR"))
    )
    (comp (ref "IC15")
      (value "LMP7701MF")
      (footprint "eagle-import:DBV5-L")
      (libsource (lib "eagle-import") (part "LMP7701MF"))
    )
    (comp (ref "IC16")
      (value "TXB0304RUTR")
      (footprint "eagle-import:RUT0012A")
      (libsource (lib "eagle-import") (part "TXB0304RUTR"))
    )
    (comp (ref "R51")
      (value "24")
      (footprint "eagle-import:RESC1005X40")
      (libsource (lib "eagle-import") (part "R_SMD0402"))
    )
    (comp (ref "R52")
      (value "10k")
      (footprint "eagle-import:RESC1005X40")
      (libsource (lib "eagle-import") (part "R_SMD0402"))
    )
    (comp (ref "C12")
      (value "10u")
      (footprint "eagle-import:CAPC2012X145")
      (libsource (lib "eagle-import") (part "C_SMD0805"))
    )
    (comp (ref "C13")
      (value "10u")
      (footprint "eagle-import:CAPC2012X145")
      (libsource (lib "eagle-import") (part "C_SMD0805"))
    )
    (comp (ref "C14")
      (value "1u")
      (footprint "eagle-import:CAPC1608X95")
      (libsource (lib "eagle-import") (part "C_SMD0603"))
    )
    (comp (ref "C15")
      (value "1u")
      (footprint "eagle-import:CAPC1608X95")
      (libsource (lib "eagle-import") (part "C_SMD0603"))
    )
    (comp (ref "C16")
      (value "1u")
      (footprint "eagle-import:CAPC1608X95")
      (libsource (lib "eagle-import") (part "C_SMD0603"))
    )
    (comp (ref "C17")
      (value "22u")
      (footprint "eagle-import:CAPC3225X280")
      (libsource (lib "eagle-import") (part "C_SMD1210"))
    )
    (comp (ref "C18")
      (value "10u")
      (footprint "eagle-import:CAPC2012X145")
      (libsource (lib "eagle-import") (part "C_SMD0805"))
    )
    (comp (ref "C19")
      (value "1u")
      (footprint "eagle-import:CAPC1608X95")
      (libsource (lib "eagle-import") (part "C_SMD0603"))
    )
    (comp (ref "C20")
      (value "1u")
      (footprint "eagle-import:CAPC1608X95")
      (libsource (lib "eagle-import") (part "C_SMD0603"))
    )
    (comp (ref "C21")
      (value "10u")
      (footprint "eagle-import:CAPC2012X145")
      (libsource (lib "eagle-import") (part "C_SMD0805"))
    )
    (comp (ref "C22")
      (value "1u")
      (footprint "eagle-import:CAPC1608X95")
      (libsource (lib "eagle-import") (part "C_SMD0603"))
    )
    (comp (ref "C23")
      (value "0.1u")
      (footprint "eagle-import:CAPC1005X55")
      (libsource (lib "eagle-import") (part "C_SMD0402"))
    )
    (comp (ref "C24")
      (value "1n")
      (footprint "eagle-import:CAPC1005X55")
      (libsource (lib "eagle-import") (part "C_SMD0402"))
    )
    (comp (ref "C25")
      (value "1n")
      (footprint "eagle-import:CAPC1005X55")
      (libsource (lib "eagle-import") (part "C_SMD0402"))
    )
    (comp (ref "IC5")
      (value "ADS8694TSSOP38")
      (footprint "eagle-import:TSSOP38")
      (libsource (lib "eagle-import") (part "ADS8694TSSOP38"))
    )
    (comp (ref "IC6")
      (value "OPA2388DGK8_L")
      (footprint "eagle-import:DGK8-L")
      (libsource (lib "eagle-import") (part "OPA2388DGK8_L"))
    )
    (comp (ref "R20")
      (value "24")
      (footprint "eagle-import:RESC1005X40")
      (libsource (lib "eagle-import") (part "R_SMD0402"))
    )
    (comp (ref "R21")
      (value "24")
      (footprint "eagle-import:RESC1005X40")
      (libsource (lib "eagle-import") (part "R_SMD0402"))
    )
    (comp (ref "TP3")
      (value "TPSQTP06R")
      (footprint "eagle-import:TP06R")
      (libsource (lib "eagle-import") (part "TPSQTP06R"))
    )
    (comp (ref "TP4")
      (value "TPSQTP06R")
      (footprint "eagle-import:TP06R")
      (libsource (lib "eagle-import") (part "TPSQTP06R"))
    )
  )
  (nets
    (net (code "1") (name "+3V3") (class "Default")
      (node (ref "C1") (pin "1") (pinfunction "1_1") (pintype "passive"))
      (node (ref "C21") (pin "1") (pinfunction "1_1") (pintype "passive"))
      (node (ref "C22") (pin "1") (pinfunction "1_1") (pintype "passive"))
      (node (ref "C26") (pin "1") (pinfunction "1_1") (pintype "passive"))
      (node (ref "C27") (pin "2") (pinfunction "2_2") (pintype "passive"))
      (node (ref "C38") (pin "1") (pinfunction "1_1") (pintype "passive"))
      (node (ref "C46") (pin "1") (pinfunction "1_1") (pintype "passive"))
      (node (ref "C51") (pin "1") (pinfunction "1_1") (pintype "passive"))
      (node (ref "IC11") (pin "8") (pinfunction "VCC_8") (pintype "bidirectional"))
      (node (ref "IC14") (pin "14") (pinfunction "VCC_14") (pintype "power_in"))
      (node (ref "IC16") (pin "11") (pinfunction "VCCB_11") (pintype "power_in"))
      (node (ref "IC2") (pin "8") (pinfunction "V+_8") (pintype "power_in"))
      (node (ref "IC5") (pin "34") (pinfunction "DVDD_34") (pintype "power_in"))
      (node (ref "IC7") (pin "3") (pinfunction "VDD_3") (pintype "power_in"))
      (node (ref "J1") (pin "1") (pinfunction "1_1") (pintype "passive"))
      (node (ref "P2") (pin "5") (pinfunction "5_5") (pintype "passive"))
      (node (ref "P3") (pin "1") (pinfunction "1_1") (pintype "passive"))
      (node (ref "P9") (pin "3") (pinfunction "3_3") (pintype "passive"))
      (node (ref "P9") (pin "4") (pinfunction "4_4") (pintype "passive"))
      (node (ref "R10") (pin "2") (pinfunction "2_2") (pintype "passive"))
      (node (ref "R22") (pin "2") (pinfunction "2_2") (pintype "passive"))
      (node (ref "R23") (pin "2") (pinfunction "2_2") (pintype "passive"))
      (node (ref "R41") (pin "2") (pinfunction "2_2") (pintype "passive"))
      (node (ref "R42") (pin "2") (pinfunction "2_2") (pintype "passive"))
      (node (ref "R47") (pin "2") (pinfunction "2_2") (pintype "passive"))
      (node (ref "R48") (pin "2") (pinfunction "2_2") (pintype "passive"))
      (node (ref "R49") (pin "2") (pinfunction "2_2") (pintype "passive"))
      (node (ref "R5") (pin "1") (pinfunction "1_1") (pintype "passive"))
      (node (ref "R50") (pin "2") (pinfunction "2_2") (pintype "passive"))
      (node (ref "R54") (pin "1") (pinfunction "1_1") (pintype "passive"))
    )
    (net (code "2") (name "+5V") (class "Default")
      (node (ref "C36") (pin "1") (pinfunction "1_1") (pintype "passive"))
      (node (ref "IC12") (pin "3") (pinfunction "VIN_3") (pintype "input"))
      (node (ref "P9") (pin "7") (pinfunction "7_7") (pintype "passive"))
      (node (ref "P9") (pin "8") (pinfunction "8_8") (pintype "passive"))
    )
    (net (code "3") (name "BUTTON_LED_OD") (class "Default")
      (node (ref "J1") (pin "2") (pinfunction "2_2") (pintype "passive"))
      (node (ref "R38") (pin "2") (pinfunction "2_2") (pintype "passive"))
    )
    (net (code "4") (name "CS_ADC") (class "Default")
      (node (ref "IC5") (pin "38") (pinfunction "CS_N_38") (pintype "input"))
      (node (ref "P9") (pin "25") (pinfunction "25_25") (pintype "passive"))
    )
    (net (code "5") (name "CS_DAC") (class "Default")
      (node (ref "IC10") (pin "6") (pinfunction "~{SYNC}_6") (pintype "input"))
      (node (ref "P9") (pin "31") (pinfunction "31_31") (pintype "passive"))
    )
    (net (code "6") (name "EN_HRVST") (class "Default")
      (node (ref "R32") (pin "2") (pinfunction "2_2") (pintype "passive"))
      (node (ref "T2") (pin "1") (pinfunction "G_1") (pintype "passive"))
    )
    (net (code "7") (name "EN_LVLCNV") (class "Default")
      (node (ref "IC16") (pin "12") (pinfunction "OE_12") (pintype "input"))
      (node (ref "R37") (pin "1") (pinfunction "1_1") (pintype "passive"))
    )
    (net (code "8") (name "EN_MPPT#") (class "Default")
      (node (ref "R34") (pin "2") (pinfunction "2_2") (pintype "passive"))
      (node (ref "S2") (pin "1") (pinfunction "IN1_1") (pintype "passive"))
      (node (ref "S2") (pin "5") (pinfunction "IN2_5") (pintype "passive"))
    )
    (net (code "9") (name "EN_V_ANLG") (class "Default")
      (node (ref "IC12") (pin "12") (pinfunction "EN_P_12") (pintype "input"))
      (node (ref "IC12") (pin "8") (pinfunction "EN_N_8") (pintype "input"))
      (node (ref "R40") (pin "1") (pinfunction "1_1") (pintype "passive"))
    )
    (net (code "10") (name "EN_V_FIX") (class "Default")
      (node (ref "P9") (pin "16") (pinfunction "16_16") (pintype "passive"))
      (node (ref "P9") (pin "29") (pinfunction "29_29") (pintype "passive"))
      (node (ref "S4") (pin "4") (pinfunction "SEL_4") (pintype "bidirectional"))
    )
    (net (code "11") (name "GND") (class "Default")
      (node (ref "C1") (pin "2") (pinfunction "2_2") (pintype "passive"))
      (node (ref "C11") (pin "2") (pinfunction "2_2") (pintype "passive"))
      (node (ref "C12") (pin "2") (pinfunction "2_2") (pintype "passive"))
      (node (ref "C13") (pin "2") (pinfunction "2_2") (pintype "passive"))
      (node (ref "C14") (pin "2") (pinfunction "2_2") (pintype "passive"))
      (node (ref "C15") (pin "2") (pinfunction "2_2") (pintype "passive"))
      (node (ref "C16") (pin "2") (pinfunction "2_2") (pintype "passive"))
      (node (ref "C17") (pin "2") (pinfunction "2_2") (pintype "passive"))
      (node (ref "C18") (pin "2") (pinfunction "2_2") (pintype "passive"))
      (node (ref "C19") (pin "2") (pinfunction "2_2") (pintype "passive"))
      (node (ref "C2") (pin "2") (pinfunction "2_2") (pintype "passive"))
      (node (ref "C20") (pin "2") (pinfunction "2_2") (pintype "passive"))
      (node (ref "C21") (pin "2") (pinfunction "2_2") (pintype "passive"))
      (node (ref "C22") (pin "2") (pinfunction "2_2") (pintype "passive"))
      (node (ref "C23") (pin "2") (pinfunction "2_2") (pintype "passive"))
      (node (ref "C26") (pin "2") (pinfunction "2_2") (pintype "passive"))
      (node (ref "C27") (pin "1") (pinfunction "1_1") (pintype "passive"))
      (node (ref "C28") (pin "2") (pinfunction "2_2") (pintype "passive"))
      (node (ref "C3") (pin "2") (pinfunction "2_2") (pintype "passive"))
      (node (ref "C30") (pin "2") (pinfunction "2_2") (pintype "passive"))
      (node (ref "C31") (pin "2") (pinfunction "2_2") (pintype "passive"))
      (node (ref "C32") (pin "2") (pinfunction "2_2") (pintype "passive"))
      (node (ref "C33") (pin "2") (pinfunction "2_2") (pintype "passive"))
      (node (ref "C34") (pin "2") (pinfunction "2_2") (pintype "passive"))
      (node (ref "C35") (pin "2") (pinfunction "2_2") (pintype "passive"))
      (node (ref "C36") (pin "2") (pinfunction "2_2") (pintype "passive"))
      (node (ref "C38") (pin "2") (pinfunction "2_2") (pintype "passive"))
      (node (ref "C39") (pin "2") (pinfunction "2_2") (pintype "passive"))
      (node (ref "C40") (pin "2") (pinfunction "2_2") (pintype "passive"))
      (node (ref "C41") (pin "2") (pinfunction "2_2") (pintype "passive"))
      (node (ref "C42") (pin "2") (pinfunction "2_2") (pintype "passive"))
      (node (ref "C43") (pin "2") (pinfunction "2_2") (pintype "passive"))
      (node (ref "C44") (pin "2") (pinfunction "2_2") (pintype "passive"))
      (node (ref "C45") (pin "2") (pinfunction "2_2") (pintype "passive"))
      (node (ref "C46") (pin "2") (pinfunction "2_2") (pintype "passive"))
      (node (ref "C48") (pin "2") (pinfunction "2_2") (pintype "passive"))
      (node (ref "C49") (pin "2") (pinfunction "2_2") (pintype "passive"))
      (node (ref "C50") (pin "2") (pinfunction "2_2") (pintype "passive"))
      (node (ref "C51") (pin "2") (pinfunction "2_2") (pintype "passive"))
      (node (ref "C52") (pin "2") (pinfunction "2_2") (pintype "passive"))
      (node (ref "C53") (pin "2") (pinfunction "2_2") (pintype "passive"))
      (node (ref "C6") (pin "2") (pinfunction "2_2") (pintype "passive"))
      (node (ref "C7") (pin "2") (pinfunction "2_2") (pintype "passive"))
      (node (ref "C8") (pin "2") (pinfunction "2_2") (pintype "passive"))
      (node (ref "D2") (pin "2") (pinfunction "A_2") (pintype "passive"))
      (node (ref "IC1") (pin "6") (pinfunction "REF_6") (pintype "input"))
      (node (ref "IC10") (pin "3") (pinfunction "GND_3") (pintype "power_in"))
      (node (ref "IC10") (pin "4") (pinfunction "~{LDAC}_4") (pintype "passive"))
      (node (ref "IC11") (pin "1") (pinfunction "A0_1") (pintype "bidirectional"))
      (node (ref "IC11") (pin "2") (pinfunction "A1_2") (pintype "bidirectional"))
      (node (ref "IC11") (pin "4") (pinfunction "VSS_4") (pintype "bidirectional"))
      (node (ref "IC12") (pin "1") (pinfunction "PGOOD_1") (pintype "output"))
      (node (ref "IC12") (pin "13") (pinfunction "EP_GND_13") (pintype "power_in"))
      (node (ref "IC12") (pin "4") (pinfunction "GND_4") (pintype "power_in"))
      (node (ref "IC13") (pin "1") (pinfunction "VSS_2_1") (pintype "power_in"))
      (node (ref "IC13") (pin "12") (pinfunction "AVSS_12") (pintype "power_in"))
      (node (ref "IC13") (pin "13") (pinfunction "VSS_13") (pintype "power_in"))
      (node (ref "IC13") (pin "17") (pinfunction "EPAD_17") (pintype "power_in"))
      (node (ref "IC13") (pin "5") (pinfunction "OT_PROG_5") (pintype "input"))
      (node (ref "IC14") (pin "1") (pinfunction "1OE_N_1") (pintype "input"))
      (node (ref "IC14") (pin "10") (pinfunction "3OE_N_10") (pintype "input"))
      (node (ref "IC14") (pin "13") (pinfunction "4OE_N_13") (pintype "input"))
      (node (ref "IC14") (pin "4") (pinfunction "2OE_N_4") (pintype "input"))
      (node (ref "IC14") (pin "7") (pinfunction "GND_7") (pintype "power_in"))
      (node (ref "IC15") (pin "2") (pinfunction "V-_2") (pintype "power_in"))
      (node (ref "IC16") (pin "6") (pinfunction "GND_6") (pintype "power_in"))
      (node (ref "IC2") (pin "4") (pinfunction "V-_4") (pintype "power_in"))
      (node (ref "IC3") (pin "6") (pinfunction "REF_6") (pintype "input"))
      (node (ref "IC4") (pin "4") (pinfunction "V-_4") (pintype "power_in"))
      (node (ref "IC5") (pin "17") (pinfunction "AIN_0GND_17") (pintype "power_in"))
      (node (ref "IC5") (pin "19") (pinfunction "AIN_1GND_19") (pintype "power_in"))
      (node (ref "IC5") (pin "20") (pinfunction "AIN2_GND_20") (pintype "power_in"))
      (node (ref "IC5") (pin "22") (pinfunction "AIN_3GND_22") (pintype "power_in"))
      (node (ref "IC5") (pin "28") (pinfunction "AGND_2_28") (pintype "power_in"))
      (node (ref "IC5") (pin "29") (pinfunction "AGND_3_29") (pintype "power_in"))
      (node (ref "IC5") (pin "3") (pinfunction "DAISY_3") (pintype "input"))
      (node (ref "IC5") (pin "31") (pinfunction "AGND_4_31") (pintype "power_in"))
      (node (ref "IC5") (pin "32") (pinfunction "AGND_5_32") (pintype "power_in"))
      (node (ref "IC5") (pin "33") (pinfunction "DGND_33") (pintype "power_in"))
      (node (ref "IC5") (pin "4") (pinfunction "REFSEL_N_4") (pintype "input"))
      (node (ref "IC5") (pin "6") (pinfunction "REFGND_6") (pintype "power_in"))
      (node (ref "IC5") (pin "8") (pinfunction "AGND_8") (pintype "power_in"))
      (node (ref "IC6") (pin "4") (pinfunction "V-_4") (pintype "power_in"))
      (node (ref "IC7") (pin "2") (pinfunction "GND_2") (pintype "power_in"))
      (node (ref "IC7") (pin "6") (pinfunction "A0_6") (pintype "input"))
      (node (ref "IC8") (pin "2") (pinfunction "GND_2") (pintype "passive"))
      (node (ref "J1") (pin "4") (pinfunction "4_4") (pintype "passive"))
      (node (ref "J1") (pin "5") (pinfunction "MNT_1_5") (pintype "passive"))
      (node (ref "J1") (pin "6") (pinfunction "MNT_2_6") (pintype "passive"))
      (node (ref "P1") (pin "1") (pinfunction "1_1") (pintype "passive"))
      (node (ref "P1") (pin "3") (pinfunction "3_3") (pintype "passive"))
      (node (ref "P2") (pin "16") (pinfunction "16_16") (pintype "passive"))
      (node (ref "P2") (pin "2") (pinfunction "2_2") (pintype "passive"))
      (node (ref "P2") (pin "7") (pinfunction "7_7") (pintype "passive"))
      (node (ref "P3") (pin "3") (pinfunction "3_3") (pintype "passive"))
      (node (ref "P3") (pin "4") (pinfunction "4_4") (pintype "passive"))
      (node (ref "P4") (pin "1") (pinfunction "1_1") (pintype "passive"))
      (node (ref "P4") (pin "2") (pinfunction "2_2") (pintype "passive"))
      (node (ref "P4") (pin "3") (pinfunction "3_3") (pintype "passive"))
      (node (ref "P4") (pin "4") (pinfunction "4_4") (pintype "passive"))
      (node (ref "P8") (pin "1") (pinfunction "1_1") (pintype "passive"))
      (node (ref "P8") (pin "2") (pinfunction "2_2") (pintype "passive"))
      (node (ref "P9") (pin "1") (pinfunction "1_1") (pintype "passive"))
      (node (ref "P9") (pin "2") (pinfunction "2_2") (pintype "passive"))
      (node (ref "P9") (pin "43") (pinfunction "43_43") (pintype "passive"))
      (node (ref "P9") (pin "44") (pinfunction "44_44") (pintype "passive"))
      (node (ref "P9") (pin "45") (pinfunction "45_45") (pintype "passive"))
      (node (ref "P9") (pin "46") (pinfunction "46_46") (pintype "passive"))
      (node (ref "R16") (pin "2") (pinfunction "2_2") (pintype "passive"))
      (node (ref "R26") (pin "2") (pinfunction "2_2") (pintype "passive"))
      (node (ref "R29") (pin "2") (pinfunction "2_2") (pintype "passive"))
      (node (ref "R44") (pin "1") (pinfunction "1_1") (pintype "passive"))
      (node (ref "R46") (pin "1") (pinfunction "1_1") (pintype "passive"))
      (node (ref "R6") (pin "2") (pinfunction "2_2") (pintype "passive"))
      (node (ref "ROK1") (pin "1") (pinfunction "1_1") (pintype "passive"))
      (node (ref "ROV1") (pin "1") (pinfunction "1_1") (pintype "passive"))
      (node (ref "RUV1") (pin "1") (pinfunction "1_1") (pintype "passive"))
      (node (ref "S1") (pin "3") (pinfunction "GND_3") (pintype "passive"))
      (node (ref "S2") (pin "3") (pinfunction "GND_3") (pintype "passive"))
      (node (ref "S4") (pin "3") (pinfunction "GND_3") (pintype "power_in"))
      (node (ref "T1") (pin "2") (pinfunction "S_2") (pintype "passive"))
      (node (ref "T2") (pin "2") (pinfunction "S_2") (pintype "passive"))
      (node (ref "T5") (pin "2") (pinfunction "S_2") (pintype "passive"))
      (node (ref "T6") (pin "2") (pinfunction "S_2") (pintype "passive"))
      (node (ref "T7") (pin "2") (pinfunction "S_2") (pintype "passive"))
    )
    (net (code "12") (name "GPIO0_BB") (class "Default")
      (node (ref "D5") (pin "2") (pinfunction "C_2") (pintype "passive"))
      (node (ref "P8") (pin "45") (pinfunction "45_45") (pintype "passive"))
    )
    (net (code "13") (name "GPIO0_TARGET") (class "Default")
      (node (ref "IC14") (pin "12") (pinfunction "4A_12") (pintype "input"))
      (node (ref "P2") (pin "10") (pinfunction "10_10") (pintype "passive"))
    )
    (net (code "14") (name "GPIO1_BB") (class "Default")
      (node (ref "D3") (pin "2") (pinfunction "C_2") (pintype "passive"))
      (node (ref "P8") (pin "46") (pinfunction "46_46") (pintype "passive"))
    )
    (net (code "15") (name "GPIO1_TARGET") (class "Default")
      (node (ref "IC14") (pin "5") (pinfunction "2A_5") (pintype "input"))
      (node (ref "P2") (pin "14") (pinfunction "14_14") (pintype "passive"))
    )
    (net (code "16") (name "GPIO2_BB") (class "Default")
      (node (ref "D6") (pin "2") (pinfunction "C_2") (pintype "passive"))
      (node (ref "P8") (pin "43") (pinfunction "43_43") (pintype "passive"))
    )
    (net (code "17") (name "GPIO2_TARGET") (class "Default")
      (node (ref "IC14") (pin "9") (pinfunction "3A_9") (pintype "input"))
      (node (ref "P2") (pin "8") (pinfunction "8_8") (pintype "passive"))
    )
    (net (code "18") (name "GPIO3_BB") (class "Default")
      (node (ref "D4") (pin "2") (pinfunction "C_2") (pintype "passive"))
      (node (ref "P8") (pin "44") (pinfunction "44_44") (pintype "passive"))
    )
    (net (code "19") (name "GPIO3_TARGET") (class "Default")
      (node (ref "IC14") (pin "2") (pinfunction "1A_2") (pintype "input"))
      (node (ref "P2") (pin "12") (pinfunction "12_12") (pintype "passive"))
    )
    (net (code "20") (name "I2C1_SCL") (class "Default")
      (node (ref "IC7") (pin "5") (pinfunction "SCL_5") (pintype "input"))
      (node (ref "P9") (pin "17") (pinfunction "17_17") (pintype "passive"))
      (node (ref "R22") (pin "1") (pinfunction "1_1") (pintype "passive"))
    )
    (net (code "21") (name "I2C1_SDA") (class "Default")
      (node (ref "IC7") (pin "4") (pinfunction "SDA_4") (pintype "input"))
      (node (ref "P9") (pin "18") (pinfunction "18_18") (pintype "passive"))
      (node (ref "R23") (pin "1") (pinfunction "1_1") (pintype "passive"))
    )
    (net (code "22") (name "I2C2_SCL") (class "Default")
      (node (ref "IC11") (pin "6") (pinfunction "SCL_6") (pintype "bidirectional"))
      (node (ref "P9") (pin "19") (pinfunction "19_19") (pintype "passive"))
      (node (ref "R47") (pin "1") (pinfunction "1_1") (pintype "passive"))
    )
    (net (code "23") (name "I2C2_SDA") (class "Default")
      (node (ref "IC11") (pin "5") (pinfunction "SDA_5") (pintype "bidirectional"))
      (node (ref "P9") (pin "20") (pinfunction "20_20") (pintype "passive"))
      (node (ref "R48") (pin "1") (pinfunction "1_1") (pintype "passive"))
    )
    (net (code "24") (name "LED_BUTTON") (class "Default")
      (node (ref "R53") (pin "1") (pinfunction "1_1") (pintype "passive"))
      (node (ref "T7") (pin "1") (pinfunction "G_1") (pintype "passive"))
    )
    (net (code "25") (name "LED_USR1") (class "Default")
      (node (ref "R35") (pin "1") (pinfunction "1_1") (pintype "passive"))
      (node (ref "T5") (pin "1") (pinfunction "G_1") (pintype "passive"))
    )
    (net (code "26") (name "LED_USR2") (class "Default")
      (node (ref "R36") (pin "1") (pinfunction "1_1") (pintype "passive"))
      (node (ref "T6") (pin "1") (pinfunction "G_1") (pintype "passive"))
    )
    (net (code "27") (name "MISO") (class "Default")
      (node (ref "IC5") (pin "36") (pinfunction "SDO_36") (pintype "output"))
      (node (ref "P9") (pin "27") (pinfunction "27_27") (pintype "passive"))
    )
    (net (code "28") (name "MOSI") (class "Default")
      (node (ref "IC10") (pin "8") (pinfunction "DIN_8") (pintype "input"))
      (node (ref "IC5") (pin "1") (pinfunction "SDI_1") (pintype "input"))
      (node (ref "P9") (pin "30") (pinfunction "30_30") (pintype "passive"))
    )
    (net (code "29") (name "Net-(D1-A)") (class "Default")
      (node (ref "D1") (pin "2") (pinfunction "A_2") (pintype "passive"))
      (node (ref "T4") (pin "3") (pinfunction "D_3") (pintype "passive"))
    )
    (net (code "30") (name "Net-(D3-A)") (class "Default")
      (node (ref "D3") (pin "1") (pinfunction "A_1") (pintype "passive"))
      (node (ref "IC14") (pin "6") (pinfunction "2Y_6") (pintype "tri_state"))
    )
    (net (code "31") (name "Net-(D4-A)") (class "Default")
      (node (ref "D4") (pin "1") (pinfunction "A_1") (pintype "passive"))
      (node (ref "IC14") (pin "3") (pinfunction "1Y_3") (pintype "tri_state"))
    )
    (net (code "32") (name "Net-(D5-A)") (class "Default")
      (node (ref "D5") (pin "1") (pinfunction "A_1") (pintype "passive"))
      (node (ref "IC14") (pin "11") (pinfunction "4Y_11") (pintype "tri_state"))
    )
    (net (code "33") (name "Net-(D6-A)") (class "Default")
      (node (ref "D6") (pin "1") (pinfunction "A_1") (pintype "passive"))
      (node (ref "IC14") (pin "8") (pinfunction "3Y_8") (pintype "tri_state"))
    )
    (net (code "34") (name "Net-(IC1-RG)") (class "Default")
      (node (ref "IC1") (pin "2") (pinfunction "RG_2") (pintype "passive"))
      (node (ref "R1") (pin "2") (pinfunction "2_2") (pintype "passive"))
    )
    (net (code "35") (name "Net-(IC1-RG_2)") (class "Default")
      (node (ref "IC1") (pin "3") (pinfunction "RG_2_3") (pintype "passive"))
      (node (ref "R1") (pin "1") (pinfunction "1_1") (pintype "passive"))
    )
    (net (code "36") (name "Net-(IC2A-IN+)") (class "Default")
      (node (ref "C5") (pin "1") (pinfunction "1_1") (pintype "passive"))
      (node (ref "IC2") (pin "3") (pinfunction "IN+_3") (pintype "input"))
      (node (ref "R4") (pin "2") (pinfunction "2_2") (pintype "passive"))
      (node (ref "R7") (pin "2") (pinfunction "2_2") (pintype "passive"))
    )
    (net (code "37") (name "Net-(IC2A-IN-)") (class "Default")
      (node (ref "IC2") (pin "2") (pinfunction "IN-_2") (pintype "input"))
      (node (ref "R5") (pin "2") (pinfunction "2_2") (pintype "passive"))
      (node (ref "R6") (pin "1") (pinfunction "1_1") (pintype "passive"))
    )
    (net (code "38") (name "Net-(IC2A-OUT)") (class "Default")
      (node (ref "C5") (pin "2") (pinfunction "2_2") (pintype "passive"))
      (node (ref "IC2") (pin "1") (pinfunction "OUT_1") (pintype "output"))
      (node (ref "R7") (pin "1") (pinfunction "1_1") (pintype "passive"))
      (node (ref "R8") (pin "2") (pinfunction "2_2") (pintype "passive"))
    )
    (net (code "39") (name "Net-(IC2B-IN-)") (class "Default")
      (node (ref "C4") (pin "1") (pinfunction "1_1") (pintype "passive"))
      (node (ref "IC2") (pin "6") (pinfunction "IN-_6") (pintype "input"))
      (node (ref "R3") (pin "1") (pinfunction "1_1") (pintype "passive"))
      (node (ref "R4") (pin "1") (pinfunction "1_1") (pintype "passive"))
    )
    (net (code "40") (name "Net-(IC2B-OUT)") (class "Default")
      (node (ref "C4") (pin "2") (pinfunction "2_2") (pintype "passive"))
      (node (ref "IC2") (pin "7") (pinfunction "OUT_7") (pintype "output"))
      (node (ref "R3") (pin "2") (pinfunction "2_2") (pintype "passive"))
    )
    (net (code "41") (name "Net-(IC3-RG)") (class "Default")
      (node (ref "IC3") (pin "2") (pinfunction "RG_2") (pintype "passive"))
      (node (ref "R12") (pin "1") (pinfunction "1_1") (pintype "passive"))
    )
    (net (code "42") (name "Net-(IC3-RG_2)") (class "Default")
      (node (ref "IC3") (pin "3") (pinfunction "RG_2_3") (pintype "passive"))
      (node (ref "R12") (pin "2") (pinfunction "2_2") (pintype "passive"))
    )
    (net (code "43") (name "Net-(IC4A-IN-)") (class "Default")
      (node (ref "C9") (pin "1") (pinfunction "1_1") (pintype "passive"))
      (node (ref "IC4") (pin "2") (pinfunction "IN-_2") (pintype "input"))
      (node (ref "R14") (pin "2") (pinfunction "2_2") (pintype "passive"))
    )
    (net (code "44") (name "Net-(IC4A-OUT)") (class "Default")
      (node (ref "C9") (pin "2") (pinfunction "2_2") (pintype "passive"))
      (node (ref "IC4") (pin "1") (pinfunction "OUT_1") (pintype "output"))
      (node (ref "R13") (pin "2") (pinfunction "2_2") (pintype "passive"))
    )
    (net (code "45") (name "Net-(IC4B-IN+)") (class "Default")
      (node (ref "IC4") (pin "5") (pinfunction "IN+_5") (pintype "input"))
      (node (ref "R15") (pin "2") (pinfunction "2_2") (pintype "passive"))
      (node (ref "T3") (pin "3") (pinfunction "D_3") (pintype "passive"))
    )
    (net (code "46") (name "Net-(IC4B-IN-)") (class "Default")
      (node (ref "C10") (pin "1") (pinfunction "1_1") (pintype "passive"))
      (node (ref "IC4") (pin "6") (pinfunction "IN-_6") (pintype "input"))
      (node (ref "R17") (pin "2") (pinfunction "2_2") (pintype "passive"))
    )
    (net (code "47") (name "Net-(IC4B-OUT)") (class "Default")
      (node (ref "C10") (pin "2") (pinfunction "2_2") (pintype "passive"))
      (node (ref "IC4") (pin "7") (pinfunction "OUT_7") (pintype "output"))
      (node (ref "R18") (pin "2") (pinfunction "2_2") (pintype "passive"))
    )
    (net (code "48") (name "Net-(IC5-AUX_GND)") (class "Default")
      (node (ref "IC5") (pin "10") (pinfunction "AUX_IN_10") (pintype "input"))
      (node (ref "IC5") (pin "11") (pinfunction "AUX_GND_11") (pintype "power_in"))
    )
    (net (code "49") (name "Net-(IC5-REFCAP)") (class "Default")
      (node (ref "C15") (pin "1") (pinfunction "1_1") (pintype "passive"))
      (node (ref "C17") (pin "1") (pinfunction "1_1") (pintype "passive"))
      (node (ref "IC5") (pin "7") (pinfunction "REFCAP_7") (pintype "passive"))
    )
    (net (code "50") (name "Net-(IC5-REFIO)") (class "Default")
      (node (ref "C13") (pin "1") (pinfunction "1_1") (pintype "passive"))
      (node (ref "IC5") (pin "5") (pinfunction "REFIO_5") (pintype "bidirectional"))
    )
    (net (code "51") (name "Net-(IC6A-OUT)") (class "Default")
      (node (ref "C25") (pin "2") (pinfunction "2_2") (pintype "passive"))
      (node (ref "IC6") (pin "1") (pinfunction "OUT_1") (pintype "output"))
      (node (ref "R21") (pin "1") (pinfunction "1_1") (pintype "passive"))
    )
    (net (code "52") (name "Net-(IC6B-OUT)") (class "Default")
      (node (ref "C24") (pin "2") (pinfunction "2_2") (pintype "passive"))
      (node (ref "IC6") (pin "7") (pinfunction "OUT_7") (pintype "output"))
      (node (ref "R20") (pin "1") (pinfunction "1_1") (pintype "passive"))
    )
    (net (code "53") (name "Net-(IC7-VOUT)") (class "Default")
      (node (ref "IC7") (pin "1") (pinfunction "VOUT_1") (pintype "output"))
      (node (ref "R24") (pin "1") (pinfunction "1_1") (pintype "passive"))
    )
    (net (code "54") (name "Net-(IC8-NR{slash}FB)") (class "Default")
      (node (ref "IC8") (pin "4") (pinfunction "NR/FB_4") (pintype "input"))
      (node (ref "R24") (pin "2") (pinfunction "2_2") (pintype "passive"))
      (node (ref "R25") (pin "2") (pinfunction "2_2") (pintype "passive"))
      (node (ref "R26") (pin "1") (pinfunction "1_1") (pintype "passive"))
    )
    (net (code "55") (name "Net-(IC8-OUT)") (class "Default")
      (node (ref "C52") (pin "1") (pinfunction "1_1") (pintype "passive"))
      (node (ref "IC8") (pin "5") (pinfunction "OUT_5") (pintype "output"))
      (node (ref "R25") (pin "1") (pinfunction "1_1") (pintype "passive"))
      (node (ref "S4") (pin "1") (pinfunction "D_1") (pintype "bidirectional"))
    )
    (net (code "56") (name "Net-(IC9-IN+)") (class "Default")
      (node (ref "IC9") (pin "3") (pinfunction "IN+_3") (pintype "input"))
      (node (ref "R28") (pin "1") (pinfunction "1_1") (pintype "passive"))
      (node (ref "R29") (pin "1") (pinfunction "1_1") (pintype "passive"))
    )
    (net (code "57") (name "Net-(IC9-IN-)") (class "Default")
      (node (ref "C29") (pin "1") (pinfunction "1_1") (pintype "passive"))
      (node (ref "IC9") (pin "4") (pinfunction "IN-_4") (pintype "input"))
      (node (ref "R27") (pin "1") (pinfunction "1_1") (pintype "passive"))
      (node (ref "R30") (pin "2") (pinfunction "2_2") (pintype "passive"))
    )
    (net (code "58") (name "Net-(IC10-~{CLR})") (class "Default")
      (node (ref "IC10") (pin "5") (pinfunction "~{CLR}_5") (pintype "input"))
      (node (ref "R31") (pin "2") (pinfunction "2_2") (pintype "passive"))
    )
    (net (code "59") (name "Net-(IC11-A2)") (class "Default")
      (node (ref "IC11") (pin "3") (pinfunction "A2_3") (pintype "bidirectional"))
      (node (ref "R49") (pin "1") (pinfunction "1_1") (pintype "passive"))
    )
    (net (code "60") (name "Net-(IC11-WP)") (class "Default")
      (node (ref "IC11") (pin "7") (pinfunction "WP_7") (pintype "bidirectional"))
      (node (ref "R50") (pin "1") (pinfunction "1_1") (pintype "passive"))
      (node (ref "WP") (pin "TP") (pinfunction "TP_TP") (pintype "input"))
    )
    (net (code "61") (name "Net-(IC12-C1_N)") (class "Default")
      (node (ref "C37") (pin "2") (pinfunction "2_2") (pintype "passive"))
      (node (ref "IC12") (pin "9") (pinfunction "C1_N_9") (pintype "input"))
    )
    (net (code "62") (name "Net-(IC12-C1_P)") (class "Default")
      (node (ref "C37") (pin "1") (pinfunction "1_1") (pintype "passive"))
      (node (ref "IC12") (pin "10") (pinfunction "C1_P_10") (pintype "input"))
    )
    (net (code "63") (name "Net-(IC12-CP)") (class "Default")
      (node (ref "C41") (pin "1") (pinfunction "1_1") (pintype "passive"))
      (node (ref "IC12") (pin "5") (pinfunction "CP_5") (pintype "output"))
    )
    (net (code "64") (name "Net-(IC12-FB_N)") (class "Default")
      (node (ref "IC12") (pin "7") (pinfunction "FB_N_7") (pintype "input"))
      (node (ref "R45") (pin "1") (pinfunction "1_1") (pintype "passive"))
      (node (ref "R46") (pin "2") (pinfunction "2_2") (pintype "passive"))
    )
    (net (code "65") (name "Net-(IC12-FB_P)") (class "Default")
      (node (ref "IC12") (pin "2") (pinfunction "FB_P_2") (pintype "input"))
      (node (ref "R43") (pin "1") (pinfunction "1_1") (pintype "passive"))
      (node (ref "R44") (pin "2") (pinfunction "2_2") (pintype "passive"))
    )
    (net (code "66") (name "Net-(IC13-LBST)") (class "Default")
      (node (ref "IC13") (pin "16") (pinfunction "LBST_16") (pintype "input"))
      (node (ref "L1") (pin "1") (pinfunction "1_1") (pintype "passive"))
    )
    (net (code "67") (name "Net-(IC15-IN-)") (class "Default")
      (node (ref "C47") (pin "2") (pinfunction "2_2") (pintype "passive"))
      (node (ref "IC15") (pin "4") (pinfunction "IN-_4") (pintype "input"))
      (node (ref "R52") (pin "2") (pinfunction "2_2") (pintype "passive"))
    )
    (net (code "68") (name "Net-(IC15-OUT)") (class "Default")
      (node (ref "C47") (pin "1") (pinfunction "1_1") (pintype "passive"))
      (node (ref "IC15") (pin "1") (pinfunction "OUT_1") (pintype "output"))
      (node (ref "R51") (pin "2") (pinfunction "2_2") (pintype "passive"))
      (node (ref "R52") (pin "1") (pinfunction "1_1") (pintype "passive"))
    )
    (net (code "69") (name "Net-(LED1-A)") (class "Default")
      (node (ref "LED1") (pin "2") (pinfunction "A_2") (pintype "passive"))
      (node (ref "R41") (pin "1") (pinfunction "1_1") (pintype "passive"))
    )
    (net (code "70") (name "Net-(LED1-C)") (class "Default")
      (node (ref "LED1") (pin "1") (pinfunction "C_1") (pintype "passive"))
      (node (ref "T5") (pin "3") (pinfunction "D_3") (pintype "passive"))
    )
    (net (code "71") (name "Net-(LED2-A)") (class "Default")
      (node (ref "LED2") (pin "2") (pinfunction "A_2") (pintype "passive"))
      (node (ref "R42") (pin "1") (pinfunction "1_1") (pintype "passive"))
    )
    (net (code "72") (name "Net-(LED2-C)") (class "Default")
      (node (ref "LED2") (pin "1") (pinfunction "C_1") (pintype "passive"))
      (node (ref "T6") (pin "3") (pinfunction "D_3") (pintype "passive"))
    )
    (net (code "73") (name "Net-(LED3-A)") (class "Default")
      (node (ref "LED3") (pin "2") (pinfunction "A_2") (pintype "passive"))
      (node (ref "LED4") (pin "2") (pinfunction "A_2") (pintype "passive"))
      (node (ref "R9") (pin "1") (pinfunction "1_1") (pintype "passive"))
    )
    (net (code "74") (name "Net-(LED3-C)") (class "Default")
      (node (ref "LED3") (pin "1") (pinfunction "C_1") (pintype "passive"))
      (node (ref "LED4") (pin "1") (pinfunction "C_1") (pintype "passive"))
      (node (ref "T1") (pin "3") (pinfunction "D_3") (pintype "passive"))
    )
    (net (code "75") (name "Net-(P8-Pad12)") (class "Default")
      (node (ref "P8") (pin "12") (pinfunction "12_12") (pintype "passive"))
      (node (ref "R35") (pin "2") (pinfunction "2_2") (pintype "passive"))
    )
    (net (code "76") (name "Net-(P8-Pad13)") (class "Default")
      (node (ref "P8") (pin "13") (pinfunction "13_13") (pintype "passive"))
      (node (ref "R32") (pin "1") (pinfunction "1_1") (pintype "passive"))
    )
    (net (code "77") (name "Net-(P8-Pad28)") (class "Default")
      (node (ref "P8") (pin "28") (pinfunction "28_28") (pintype "passive"))
      (node (ref "R39") (pin "2") (pinfunction "2_2") (pintype "passive"))
    )
    (net (code "78") (name "Net-(P8-Pad30)") (class "Default")
      (node (ref "P8") (pin "30") (pinfunction "30_30") (pintype "passive"))
      (node (ref "R36") (pin "2") (pinfunction "2_2") (pintype "passive"))
    )
    (net (code "79") (name "Net-(P8-Pad33)") (class "Default")
      (node (ref "P8") (pin "33") (pinfunction "33_33") (pintype "passive"))
      (node (ref "R53") (pin "2") (pinfunction "2_2") (pintype "passive"))
    )
    (net (code "80") (name "Net-(P8-Pad36)") (class "Default")
      (node (ref "P8") (pin "36") (pinfunction "36_36") (pintype "passive"))
      (node (ref "R37") (pin "2") (pinfunction "2_2") (pintype "passive"))
    )
    (net (code "81") (name "Net-(P9-Pad11)") (class "Default")
      (node (ref "P9") (pin "11") (pinfunction "11_11") (pintype "passive"))
      (node (ref "R34") (pin "1") (pinfunction "1_1") (pintype "passive"))
    )
    (net (code "82") (name "Net-(P9-Pad12)") (class "Default")
      (node (ref "P9") (pin "12") (pinfunction "12_12") (pintype "passive"))
      (node (ref "R40") (pin "2") (pinfunction "2_2") (pintype "passive"))
    )
    (net (code "83") (name "Net-(P9-Pad15)") (class "Default")
      (node (ref "P9") (pin "15") (pinfunction "15_15") (pintype "passive"))
      (node (ref "R33") (pin "1") (pinfunction "1_1") (pintype "passive"))
    )
    (net (code "84") (name "Net-(S3-A)") (class "Default")
      (node (ref "R10") (pin "1") (pinfunction "1_1") (pintype "passive"))
      (node (ref "S3") (pin "1") (pinfunction "A_1") (pintype "passive"))
    )
    (net (code "85") (name "Net-(S3-K)") (class "Default")
      (node (ref "S3") (pin "2") (pinfunction "K_2") (pintype "passive"))
      (node (ref "T2") (pin "3") (pinfunction "D_3") (pintype "passive"))
    )
    (net (code "86") (name "Net-(T1-G)") (class "Default")
      (node (ref "R8") (pin "1") (pinfunction "1_1") (pintype "passive"))
      (node (ref "T1") (pin "1") (pinfunction "G_1") (pintype "passive"))
    )
    (net (code "87") (name "Net-(T3-G)") (class "Default")
      (node (ref "R13") (pin "1") (pinfunction "1_1") (pintype "passive"))
      (node (ref "T3") (pin "1") (pinfunction "G_1") (pintype "passive"))
    )
    (net (code "88") (name "Net-(T3-S)") (class "Default")
      (node (ref "R14") (pin "1") (pinfunction "1_1") (pintype "passive"))
      (node (ref "R16") (pin "1") (pinfunction "1_1") (pintype "passive"))
      (node (ref "T3") (pin "2") (pinfunction "S_2") (pintype "passive"))
      (node (ref "TP1") (pin "TP") (pinfunction "TP_TP") (pintype "input"))
    )
    (net (code "89") (name "Net-(T4-G)") (class "Default")
      (node (ref "R18") (pin "1") (pinfunction "1_1") (pintype "passive"))
      (node (ref "T4") (pin "1") (pinfunction "G_1") (pintype "passive"))
    )
    (net (code "90") (name "Net-(T4-S)") (class "Default")
      (node (ref "R17") (pin "1") (pinfunction "1_1") (pintype "passive"))
      (node (ref "R19") (pin "2") (pinfunction "2_2") (pintype "passive"))
      (node (ref "T4") (pin "2") (pinfunction "S_2") (pintype "passive"))
      (node (ref "TP2") (pin "TP") (pinfunction "TP_TP") (pintype "input"))
    )
    (net (code "91") (name "Net-(T7-D)") (class "Default")
      (node (ref "R38") (pin "1") (pinfunction "1_1") (pintype "passive"))
      (node (ref "T7") (pin "3") (pinfunction "D_3") (pintype "passive"))
    )
    (net (code "92") (name "RST{slash}PDN_ADC") (class "Default")
      (node (ref "IC5") (pin "2") (pinfunction "RST_PD_N_2") (pintype "input"))
      (node (ref "R39") (pin "1") (pinfunction "1_1") (pintype "passive"))
    )
    (net (code "93") (name "SCLK") (class "Default")
      (node (ref "IC10") (pin "7") (pinfunction "SCLK_7") (pintype "input"))
      (node (ref "IC5") (pin "37") (pinfunction "SCLK_37") (pintype "input"))
      (node (ref "P9") (pin "28") (pinfunction "28_28") (pintype "passive"))
    )
    (net (code "94") (name "SENSE_BUTTON") (class "Default")
      (node (ref "J1") (pin "3") (pinfunction "3_3") (pintype "passive"))
      (node (ref "P8") (pin "34") (pinfunction "34_34") (pintype "passive"))
      (node (ref "R54") (pin "2") (pinfunction "2_2") (pintype "passive"))
    )
    (net (code "95") (name "SLCT_LOAD") (class "Default")
      (node (ref "R33") (pin "2") (pinfunction "2_2") (pintype "passive"))
      (node (ref "S1") (pin "1") (pinfunction "IN_1") (pintype "passive"))
    )
    (net (code "96") (name "SWDCLK_BB") (class "Default")
      (node (ref "IC16") (pin "9") (pinfunction "B2_9") (pintype "bidirectional"))
      (node (ref "P9") (pin "42") (pinfunction "42_42") (pintype "passive"))
    )
    (net (code "97") (name "SWDCLK_TARGET") (class "Default")
      (node (ref "IC16") (pin "3") (pinfunction "A2_3") (pintype "bidirectional"))
      (node (ref "P2") (pin "13") (pinfunction "13_13") (pintype "passive"))
    )
    (net (code "98") (name "SWDIO_BB") (class "Default")
      (node (ref "IC16") (pin "10") (pinfunction "B1_10") (pintype "bidirectional"))
      (node (ref "P9") (pin "41") (pinfunction "41_41") (pintype "passive"))
    )
    (net (code "99") (name "SWDIO_TARGET") (class "Default")
      (node (ref "IC16") (pin "2") (pinfunction "A1_2") (pintype "bidirectional"))
      (node (ref "P2") (pin "15") (pinfunction "15_15") (pintype "passive"))
    )
    (net (code "100") (name "UART_RX_BB") (class "Default")
      (node (ref "IC16") (pin "7") (pinfunction "B4_7") (pintype "bidirectional"))
      (node (ref "P9") (pin "26") (pinfunction "26_26") (pintype "passive"))
    )
    (net (code "101") (name "UART_RX_TARGET") (class "Default")
      (node (ref "IC16") (pin "4") (pinfunction "A3_4") (pintype "bidirectional"))
      (node (ref "P2") (pin "11") (pinfunction "11_11") (pintype "passive"))
    )
    (net (code "102") (name "UART_TX_BB") (class "Default")
      (node (ref "IC16") (pin "8") (pinfunction "B3_8") (pintype "bidirectional"))
      (node (ref "P9") (pin "24") (pinfunction "24_24") (pintype "passive"))
    )
    (net (code "103") (name "UART_TX_TARGET") (class "Default")
      (node (ref "IC16") (pin "5") (pinfunction "A4_5") (pintype "bidirectional"))
      (node (ref "P2") (pin "9") (pinfunction "9_9") (pintype "passive"))
    )
    (net (code "104") (name "VDD") (class "Default")
      (node (ref "C11") (pin "1") (pinfunction "1_1") (pintype "passive"))
      (node (ref "C12") (pin "1") (pinfunction "1_1") (pintype "passive"))
      (node (ref "C14") (pin "1") (pinfunction "1_1") (pintype "passive"))
      (node (ref "C16") (pin "1") (pinfunction "1_1") (pintype "passive"))
      (node (ref "C18") (pin "1") (pinfunction "1_1") (pintype "passive"))
      (node (ref "C19") (pin "1") (pinfunction "1_1") (pintype "passive"))
      (node (ref "C2") (pin "1") (pinfunction "1_1") (pintype "passive"))
      (node (ref "C20") (pin "1") (pinfunction "1_1") (pintype "passive"))
      (node (ref "C23") (pin "1") (pinfunction "1_1") (pintype "passive"))
      (node (ref "C28") (pin "1") (pinfunction "1_1") (pintype "passive"))
      (node (ref "C31") (pin "1") (pinfunction "1_1") (pintype "passive"))
      (node (ref "C32") (pin "1") (pinfunction "1_1") (pintype "passive"))
      (node (ref "C33") (pin "1") (pinfunction "1_1") (pintype "passive"))
      (node (ref "C34") (pin "1") (pinfunction "1_1") (pintype "passive"))
      (node (ref "C40") (pin "1") (pinfunction "1_1") (pintype "passive"))
      (node (ref "C48") (pin "1") (pinfunction "1_1") (pintype "passive"))
      (node (ref "C53") (pin "1") (pinfunction "1_1") (pintype "passive"))
      (node (ref "C6") (pin "1") (pinfunction "1_1") (pintype "passive"))
      (node (ref "C8") (pin "1") (pinfunction "1_1") (pintype "passive"))
      (node (ref "IC1") (pin "8") (pinfunction "V+_8") (pintype "power_in"))
      (node (ref "IC10") (pin "9") (pinfunction "AVDD_9") (pintype "power_in"))
      (node (ref "IC12") (pin "11") (pinfunction "OUT_P_11") (pintype "output"))
      (node (ref "IC15") (pin "5") (pinfunction "V+_5") (pintype "power_in"))
      (node (ref "IC3") (pin "8") (pinfunction "V+_8") (pintype "power_in"))
      (node (ref "IC4") (pin "8") (pinfunction "V+_8") (pintype "power_in"))
      (node (ref "IC5") (pin "30") (pinfunction "AVDD_2_30") (pintype "power_in"))
      (node (ref "IC5") (pin "9") (pinfunction "AVDD_9") (pintype "power_in"))
      (node (ref "IC6") (pin "8") (pinfunction "V+_8") (pintype "power_in"))
      (node (ref "IC8") (pin "1") (pinfunction "IN_1") (pintype "power_in"))
      (node (ref "IC8") (pin "3") (pinfunction "EN_3") (pintype "input"))
      (node (ref "IC9") (pin "5") (pinfunction "V+_5") (pintype "power_in"))
      (node (ref "R15") (pin "1") (pinfunction "1_1") (pintype "passive"))
      (node (ref "R19") (pin "1") (pinfunction "1_1") (pintype "passive"))
      (node (ref "R31") (pin "1") (pinfunction "1_1") (pintype "passive"))
      (node (ref "R43") (pin "2") (pinfunction "2_2") (pintype "passive"))
      (node (ref "S1") (pin "2") (pinfunction "VDD_2") (pintype "power_in"))
      (node (ref "S2") (pin "8") (pinfunction "VDD_8") (pintype "passive"))
      (node (ref "S4") (pin "5") (pinfunction "VDD_5") (pintype "power_in"))
      (node (ref "TP5") (pin "TP") (pinfunction "TP_TP") (pintype "input"))
    )
    (net (code "105") (name "VDD_TARGET") (class "Default")
      (node (ref "C50") (pin "1") (pinfunction "1_1") (pintype "passive"))
      (node (ref "IC16") (pin "1") (pinfunction "VCCA_1") (pintype "power_in"))
      (node (ref "R51") (pin "1") (pinfunction "1_1") (pintype "passive"))
    )
    (net (code "106") (name "VOC_SAMP") (class "Default")
      (node (ref "IC13") (pin "3") (pinfunction "VOC_SAMP_3") (pintype "input"))
      (node (ref "S2") (pin "10") (pinfunction "D1_10") (pintype "passive"))
    )
    (net (code "107") (name "VOC_VD") (class "Default")
      (node (ref "P1") (pin "4") (pinfunction "4_4") (pintype "passive"))
      (node (ref "S2") (pin "9") (pinfunction "S1B_9") (pintype "passive"))
    )
    (net (code "108") (name "VREF_SAMP") (class "Default")
      (node (ref "IC13") (pin "4") (pinfunction "VREF_SAMP_4") (pintype "input"))
      (node (ref "S2") (pin "6") (pinfunction "D2_6") (pintype "passive"))
    )
    (net (code "109") (name "VSS") (class "Default")
      (node (ref "C3") (pin "1") (pinfunction "1_1") (pintype "passive"))
      (node (ref "C30") (pin "1") (pinfunction "1_1") (pintype "passive"))
      (node (ref "C39") (pin "1") (pinfunction "1_1") (pintype "passive"))
      (node (ref "C7") (pin "1") (pinfunction "1_1") (pintype "passive"))
      (node (ref "IC1") (pin "5") (pinfunction "V-_5") (pintype "power_in"))
      (node (ref "IC12") (pin "6") (pinfunction "OUT_N_6") (pintype "output"))
      (node (ref "IC3") (pin "5") (pinfunction "V-_5") (pintype "power_in"))
      (node (ref "IC9") (pin "2") (pinfunction "V-_2") (pintype "power_in"))
      (node (ref "R45") (pin "2") (pinfunction "2_2") (pintype "passive"))
      (node (ref "TP6") (pin "TP") (pinfunction "TP_TP") (pintype "input"))
    )
    (net (code "110") (name "V_AIN") (class "Default")
      (node (ref "IC3") (pin "7") (pinfunction "OUT_7") (pintype "output"))
      (node (ref "IC5") (pin "21") (pinfunction "AIN_2P_21") (pintype "input"))
      (node (ref "TP4") (pin "TP") (pinfunction "TP_TP") (pintype "input"))
    )
    (net (code "111") (name "V_AOUT") (class "Default")
      (node (ref "IC1") (pin "7") (pinfunction "OUT_7") (pintype "output"))
      (node (ref "IC5") (pin "23") (pinfunction "AIN_3P_23") (pintype "input"))
      (node (ref "TP3") (pin "TP") (pinfunction "TP_TP") (pintype "input"))
    )
    (net (code "112") (name "V_BAT") (class "Default")
      (node (ref "IC13") (pin "14") (pinfunction "VBAT_14") (pintype "bidirectional"))
      (node (ref "P3") (pin "2") (pinfunction "2_2") (pintype "passive"))
    )
    (net (code "113") (name "V_BATOK") (class "Default")
      (node (ref "IC13") (pin "11") (pinfunction "VBAT_OK_11") (pintype "output"))
      (node (ref "P2") (pin "3") (pinfunction "3_3") (pintype "passive"))
    )
    (net (code "114") (name "V_BQ") (class "Default")
      (node (ref "C43") (pin "1") (pinfunction "1_1") (pintype "passive"))
      (node (ref "IC13") (pin "2") (pinfunction "VIN_DC_2") (pintype "input"))
      (node (ref "JP2") (pin "1") (pinfunction "1_1") (pintype "passive"))
      (node (ref "L1") (pin "2") (pinfunction "2_2") (pintype "passive"))
    )
    (net (code "115") (name "V_CREF") (class "Default")
      (node (ref "C42") (pin "1") (pinfunction "1_1") (pintype "passive"))
      (node (ref "S2") (pin "7") (pinfunction "S2B_7") (pintype "passive"))
    )
    (net (code "116") (name "V_EMU_I") (class "Default")
      (node (ref "IC10") (pin "1") (pinfunction "VOUTA_1") (pintype "output"))
      (node (ref "R28") (pin "2") (pinfunction "2_2") (pintype "passive"))
    )
    (net (code "117") (name "V_EMU_I_BIASED") (class "Default")
      (node (ref "C29") (pin "2") (pinfunction "2_2") (pintype "passive"))
      (node (ref "IC4") (pin "3") (pinfunction "IN+_3") (pintype "input"))
      (node (ref "IC9") (pin "1") (pinfunction "OUT_1") (pintype "output"))
      (node (ref "R30") (pin "1") (pinfunction "1_1") (pintype "passive"))
    )
    (net (code "118") (name "V_EMU_V") (class "Default")
      (node (ref "IC10") (pin "2") (pinfunction "VOUTB_2") (pintype "output"))
      (node (ref "S2") (pin "4") (pinfunction "S2A_4") (pintype "passive"))
    )
    (net (code "119") (name "V_H") (class "Default")
      (node (ref "D2") (pin "1") (pinfunction "C_1") (pintype "passive"))
      (node (ref "P1") (pin "2") (pinfunction "2_2") (pintype "passive"))
      (node (ref "S3") (pin "4") (pinfunction "D2_4") (pintype "passive"))
    )
    (net (code "120") (name "V_IN_SHT+") (class "Default")
      (node (ref "D1") (pin "1") (pinfunction "C_1") (pintype "passive"))
      (node (ref "IC3") (pin "4") (pinfunction "IN+_4") (pintype "input"))
      (node (ref "P2") (pin "4") (pinfunction "4_4") (pintype "passive"))
      (node (ref "R11") (pin "2") (pinfunction "2_2") (pintype "passive"))
      (node (ref "S3") (pin "6") (pinfunction "D1_6") (pintype "passive"))
    )
    (net (code "121") (name "V_IN_SHT-") (class "Default")
      (node (ref "IC3") (pin "1") (pinfunction "IN-_1") (pintype "input"))
      (node (ref "IC6") (pin "5") (pinfunction "IN+_5") (pintype "input"))
      (node (ref "JP2") (pin "2") (pinfunction "2_2") (pintype "passive"))
      (node (ref "P2") (pin "6") (pinfunction "6_6") (pintype "passive"))
      (node (ref "R11") (pin "1") (pinfunction "1_1") (pintype "passive"))
    )
    (net (code "122") (name "V_LD_SHT+") (class "Default")
      (node (ref "IC1") (pin "4") (pinfunction "IN+_4") (pintype "input"))
      (node (ref "JP1") (pin "2") (pinfunction "2_2") (pintype "passive"))
      (node (ref "R2") (pin "2") (pinfunction "2_2") (pintype "passive"))
      (node (ref "S4") (pin "2") (pinfunction "S_2") (pintype "bidirectional"))
    )
    (net (code "123") (name "V_LOAD") (class "Default")
      (node (ref "IC1") (pin "1") (pinfunction "IN-_1") (pintype "input"))
      (node (ref "IC6") (pin "3") (pinfunction "IN+_3") (pintype "input"))
      (node (ref "R2") (pin "1") (pinfunction "1_1") (pintype "passive"))
      (node (ref "S1") (pin "5") (pinfunction "D_5") (pintype "passive"))
    )
    (net (code "124") (name "V_OK_HYST") (class "Default")
      (node (ref "IC13") (pin "9") (pinfunction "OK_HYST_9") (pintype "input"))
      (node (ref "ROK2") (pin "2") (pinfunction "2_2") (pintype "passive"))
      (node (ref "ROK3") (pin "1") (pinfunction "1_1") (pintype "passive"))
    )
    (net (code "125") (name "V_OK_PROG") (class "Default")
      (node (ref "IC13") (pin "10") (pinfunction "OK_PROG_10") (pintype "input"))
      (node (ref "ROK1") (pin "2") (pinfunction "2_2") (pintype "passive"))
      (node (ref "ROK2") (pin "1") (pinfunction "1_1") (pintype "passive"))
    )
    (net (code "126") (name "V_REF_2V5") (class "Default")
      (node (ref "C35") (pin "1") (pinfunction "1_1") (pintype "passive"))
      (node (ref "IC10") (pin "10") (pinfunction "VREFIN/VREFOUT_10") (pintype "bidirectional"))
      (node (ref "R27") (pin "2") (pinfunction "2_2") (pintype "passive"))
    )
    (net (code "127") (name "V_STR") (class "Default")
      (node (ref "C44") (pin "1") (pinfunction "1_1") (pintype "passive"))
      (node (ref "C45") (pin "1") (pinfunction "1_1") (pintype "passive"))
      (node (ref "IC13") (pin "15") (pinfunction "VSTOR_15") (pintype "output"))
      (node (ref "JP1") (pin "1") (pinfunction "1_1") (pintype "passive"))
      (node (ref "S2") (pin "2") (pinfunction "S1A_2") (pintype "passive"))
    )
    (net (code "128") (name "V_SUP_DUMMY") (class "Default")
      (node (ref "IC2") (pin "5") (pinfunction "IN+_5") (pintype "input"))
      (node (ref "R9") (pin "2") (pinfunction "2_2") (pintype "passive"))
      (node (ref "S1") (pin "4") (pinfunction "S1_4") (pintype "passive"))
    )
    (net (code "129") (name "V_SUP_TARGET") (class "Default")
      (node (ref "C49") (pin "1") (pinfunction "1_1") (pintype "passive"))
      (node (ref "IC15") (pin "3") (pinfunction "IN+_3") (pintype "input"))
      (node (ref "P2") (pin "1") (pinfunction "1_1") (pintype "passive"))
      (node (ref "S1") (pin "6") (pinfunction "S2_6") (pintype "passive"))
    )
    (net (code "130") (name "V_VBAT_OV") (class "Default")
      (node (ref "IC13") (pin "6") (pinfunction "VBAT_OV_6") (pintype "input"))
      (node (ref "ROV1") (pin "2") (pinfunction "2_2") (pintype "passive"))
      (node (ref "ROV2") (pin "1") (pinfunction "1_1") (pintype "passive"))
    )
    (net (code "131") (name "V_VBAT_UV") (class "Default")
      (node (ref "IC13") (pin "8") (pinfunction "VBAT_UV_8") (pintype "input"))
      (node (ref "RUV1") (pin "2") (pinfunction "2_2") (pintype "passive"))
      (node (ref "RUV2") (pin "1") (pinfunction "1_1") (pintype "passive"))
    )
    (net (code "132") (name "V_VIN") (class "Default")
      (node (ref "C24") (pin "1") (pinfunction "1_1") (pintype "passive"))
      (node (ref "IC5") (pin "16") (pinfunction "AIN_0P_16") (pintype "input"))
      (node (ref "IC6") (pin "6") (pinfunction "IN-_6") (pintype "input"))
      (node (ref "R20") (pin "2") (pinfunction "2_2") (pintype "passive"))
    )
    (net (code "133") (name "V_VOUT") (class "Default")
      (node (ref "C25") (pin "1") (pinfunction "1_1") (pintype "passive"))
      (node (ref "IC5") (pin "18") (pinfunction "AIN_1P_18") (pintype "input"))
      (node (ref "IC6") (pin "2") (pinfunction "IN-_2") (pintype "input"))
      (node (ref "R21") (pin "2") (pinfunction "2_2") (pintype "passive"))
    )
    (net (code "134") (name "V_VRDIV") (class "Default")
      (node (ref "IC13") (pin "7") (pinfunction "VRDIV_7") (pintype "output"))
      (node (ref "ROK3") (pin "2") (pinfunction "2_2") (pintype "passive"))
      (node (ref "ROV2") (pin "2") (pinfunction "2_2") (pintype "passive"))
      (node (ref "RUV2") (pin "2") (pinfunction "2_2") (pintype "passive"))
    )
    (net (code "135") (name "unconnected-(IC5-ALARM-Pad35)") (class "Default")
      (node (ref "IC5") (pin "35") (pinfunction "ALARM_35") (pintype "output"))
    )
    (net (code "136") (name "unconnected-(IC5-NC-Pad12)") (class "Default")
      (node (ref "IC5") (pin "12") (pinfunction "NC_12") (pintype "passive"))
    )
    (net (code "137") (name "unconnected-(IC5-NC_2-Pad13)") (class "Default")
      (node (ref "IC5") (pin "13") (pinfunction "NC_2_13") (pintype "passive"))
    )
    (net (code "138") (name "unconnected-(IC5-NC_3-Pad14)") (class "Default")
      (node (ref "IC5") (pin "14") (pinfunction "NC_3_14") (pintype "passive"))
    )
    (net (code "139") (name "unconnected-(IC5-NC_4-Pad15)") (class "Default")
      (node (ref "IC5") (pin "15") (pinfunction "NC_4_15") (pintype "passive"))
    )
    (net (code "140") (name "unconnected-(IC5-NC_5-Pad24)") (class "Default")
      (node (ref "IC5") (pin "24") (pinfunction "NC_5_24") (pintype "passive"))
    )
    (net (code "141") (name "unconnected-(IC5-NC_6-Pad25)") (class "Default")
      (node (ref "IC5") (pin "25") (pinfunction "NC_6_25") (pintype "passive"))
    )
    (net (code "142") (name "unconnected-(IC5-NC_7-Pad26)") (class "Default")
      (node (ref "IC5") (pin "26") (pinfunction "NC_7_26") (pintype "passive"))
    )
    (net (code "143") (name "unconnected-(IC5-NC_8-Pad27)") (class "Default")
      (node (ref "IC5") (pin "27") (pinfunction "NC_8_27") (pintype "passive"))
    )
    (net (code "144") (name "unconnected-(P8-Pad3)") (class "Default")
      (node (ref "P8") (pin "3") (pinfunction "3_3") (pintype "passive"))
    )
    (net (code "145") (name "unconnected-(P8-Pad4)") (class "Default")
      (node (ref "P8") (pin "4") (pinfunction "4_4") (pintype "passive"))
    )
    (net (code "146") (name "unconnected-(P8-Pad5)") (class "Default")
      (node (ref "P8") (pin "5") (pinfunction "5_5") (pintype "passive"))
    )
    (net (code "147") (name "unconnected-(P8-Pad6)") (class "Default")
      (node (ref "P8") (pin "6") (pinfunction "6_6") (pintype "passive"))
    )
    (net (code "148") (name "unconnected-(P8-Pad7)") (class "Default")
      (node (ref "P8") (pin "7") (pinfunction "7_7") (pintype "passive"))
    )
    (net (code "149") (name "unconnected-(P8-Pad8)") (class "Default")
      (node (ref "P8") (pin "8") (pinfunction "8_8") (pintype "passive"))
    )
    (net (code "150") (name "unconnected-(P8-Pad9)") (class "Default")
      (node (ref "P8") (pin "9") (pinfunction "9_9") (pintype "passive"))
    )
    (net (code "151") (name "unconnected-(P8-Pad10)") (class "Default")
      (node (ref "P8") (pin "10") (pinfunction "10_10") (pintype "passive"))
    )
    (net (code "152") (name "unconnected-(P8-Pad11)") (class "Default")
      (node (ref "P8") (pin "11") (pinfunction "11_11") (pintype "passive"))
    )
    (net (code "153") (name "unconnected-(P8-Pad14)") (class "Default")
      (node (ref "P8") (pin "14") (pinfunction "14_14") (pintype "passive"))
    )
    (net (code "154") (name "unconnected-(P8-Pad15)") (class "Default")
      (node (ref "P8") (pin "15") (pinfunction "15_15") (pintype "passive"))
    )
    (net (code "155") (name "unconnected-(P8-Pad16)") (class "Default")
      (node (ref "P8") (pin "16") (pinfunction "16_16") (pintype "passive"))
    )
    (net (code "156") (name "unconnected-(P8-Pad17)") (class "Default")
      (node (ref "P8") (pin "17") (pinfunction "17_17") (pintype "passive"))
    )
    (net (code "157") (name "unconnected-(P8-Pad18)") (class "Default")
      (node (ref "P8") (pin "18") (pinfunction "18_18") (pintype "passive"))
    )
    (net (code "158") (name "unconnected-(P8-Pad19)") (class "Default")
      (node (ref "P8") (pin "19") (pinfunction "19_19") (pintype "passive"))
    )
    (net (code "159") (name "unconnected-(P8-Pad20)") (class "Default")
      (node (ref "P8") (pin "20") (pinfunction "20_20") (pintype "passive"))
    )
    (net (code "160") (name "unconnected-(P8-Pad21)") (class "Default")
      (node (ref "P8") (pin "21") (pinfunction "21_21") (pintype "passive"))
    )
    (net (code "161") (name "unconnected-(P8-Pad22)") (class "Default")
      (node (ref "P8") (pin "22") (pinfunction "22_22") (pintype "passive"))
    )
    (net (code "162") (name "unconnected-(P8-Pad23)") (class "Default")
      (node (ref "P8") (pin "23") (pinfunction "23_23") (pintype "passive"))
    )
    (net (code "163") (name "unconnected-(P8-Pad24)") (class "Default")
      (node (ref "P8") (pin "24") (pinfunction "24_24") (pintype "passive"))
    )
    (net (code "164") (name "unconnected-(P8-Pad25)") (class "Default")
      (node (ref "P8") (pin "25") (pinfunction "25_25") (pintype "passive"))
    )
    (net (code "165") (name "unconnected-(P8-Pad26)") (class "Default")
      (node (ref "P8") (pin "26") (pinfunction "26_26") (pintype "passive"))
    )
    (net (code "166") (name "unconnected-(P8-Pad27)") (class "Default")
      (node (ref "P8") (pin "27") (pinfunction "27_27") (pintype "passive"))
    )
    (net (code "167") (name "unconnected-(P8-Pad29)") (class "Default")
      (node (ref "P8") (pin "29") (pinfunction "29_29") (pintype "passive"))
    )
    (net (code "168") (name "unconnected-(P8-Pad31)") (class "Default")
      (node (ref "P8") (pin "31") (pinfunction "31_31") (pintype "passive"))
    )
    (net (code "169") (name "unconnected-(P8-Pad32)") (class "Default")
      (node (ref "P8") (pin "32") (pinfunction "32_32") (pintype "passive"))
    )
    (net (code "170") (name "unconnected-(P8-Pad35)") (class "Default")
      (node (ref "P8") (pin "35") (pinfunction "35_35") (pintype "passive"))
    )
    (net (code "171") (name "unconnected-(P8-Pad37)") (class "Default")
      (node (ref "P8") (pin "37") (pinfunction "37_37") (pintype "passive"))
    )
    (net (code "172") (name "unconnected-(P8-Pad38)") (class "Default")
      (node (ref "P8") (pin "38") (pinfunction "38_38") (pintype "passive"))
    )
    (net (code "173") (name "unconnected-(P8-Pad39)") (class "Default")
      (node (ref "P8") (pin "39") (pinfunction "39_39") (pintype "passive"))
    )
    (net (code "174") (name "unconnected-(P8-Pad40)") (class "Default")
      (node (ref "P8") (pin "40") (pinfunction "40_40") (pintype "passive"))
    )
    (net (code "175") (name "unconnected-(P8-Pad41)") (class "Default")
      (node (ref "P8") (pin "41") (pinfunction "41_41") (pintype "passive"))
    )
    (net (code "176") (name "unconnected-(P8-Pad42)") (class "Default")
      (node (ref "P8") (pin "42") (pinfunction "42_42") (pintype "passive"))
    )
    (net (code "177") (name "unconnected-(P9-Pad5)") (class "Default")
      (node (ref "P9") (pin "5") (pinfunction "5_5") (pintype "passive"))
    )
    (net (code "178") (name "unconnected-(P9-Pad6)") (class "Default")
      (node (ref "P9") (pin "6") (pinfunction "6_6") (pintype "passive"))
    )
    (net (code "179") (name "unconnected-(P9-Pad9)") (class "Default")
      (node (ref "P9") (pin "9") (pinfunction "9_9") (pintype "passive"))
    )
    (net (code "180") (name "unconnected-(P9-Pad10)") (class "Default")
      (node (ref "P9") (pin "10") (pinfunction "10_10") (pintype "passive"))
    )
    (net (code "181") (name "unconnected-(P9-Pad13)") (class "Default")
      (node (ref "P9") (pin "13") (pinfunction "13_13") (pintype "passive"))
    )
    (net (code "182") (name "unconnected-(P9-Pad14)") (class "Default")
      (node (ref "P9") (pin "14") (pinfunction "14_14") (pintype "passive"))
    )
    (net (code "183") (name "unconnected-(P9-Pad21)") (class "Default")
      (node (ref "P9") (pin "21") (pinfunction "21_21") (pintype "passive"))
    )
    (net (code "184") (name "unconnected-(P9-Pad22)") (class "Default")
      (node (ref "P9") (pin "22") (pinfunction "22_22") (pintype "passive"))
    )
    (net (code "185") (name "unconnected-(P9-Pad23)") (class "Default")
      (node (ref "P9") (pin "23") (pinfunction "23_23") (pintype "passive"))
    )
    (net (code "186") (name "unconnected-(P9-Pad32)") (class "Default")
      (node (ref "P9") (pin "32") (pinfunction "32_32") (pintype "passive"))
    )
    (net (code "187") (name "unconnected-(P9-Pad33)") (class "Default")
      (node (ref "P9") (pin "33") (pinfunction "33_33") (pintype "passive"))
    )
    (net (code "188") (name "unconnected-(P9-Pad34)") (class "Default")
      (node (ref "P9") (pin "34") (pinfunction "34_34") (pintype "passive"))
    )
    (net (code "189") (name "unconnected-(P9-Pad35)") (class "Default")
      (node (ref "P9") (pin "35") (pinfunction "35_35") (pintype "passive"))
    )
    (net (code "190") (name "unconnected-(P9-Pad36)") (class "Default")
      (node (ref "P9") (pin "36") (pinfunction "36_36") (pintype "passive"))
    )
    (net (code "191") (name "unconnected-(P9-Pad37)") (class "Default")
      (node (ref "P9") (pin "37") (pinfunction "37_37") (pintype "passive"))
    )
    (net (code "192") (name "unconnected-(P9-Pad38)") (class "Default")
      (node (ref "P9") (pin "38") (pinfunction "38_38") (pintype "passive"))
    )
    (net (code "193") (name "unconnected-(P9-Pad39)") (class "Default")
      (node (ref "P9") (pin "39") (pinfunction "39_39") (pintype "passive"))
    )
    (net (code "194") (name "unconnected-(P9-Pad40)") (class "Default")
      (node (ref "P9") (pin "40") (pinfunction "40_40") (pintype "passive"))
    )
    (net (code "195") (name "unconnected-(S3-S-Pad5)") (class "Default")
      (node (ref "S3") (pin "5") (pinfunction "S_5") (pintype "passive"))
    )
  )
)
